# OSSICommsNew.net
KiCad netlist of a schematic drawn in EAGLE
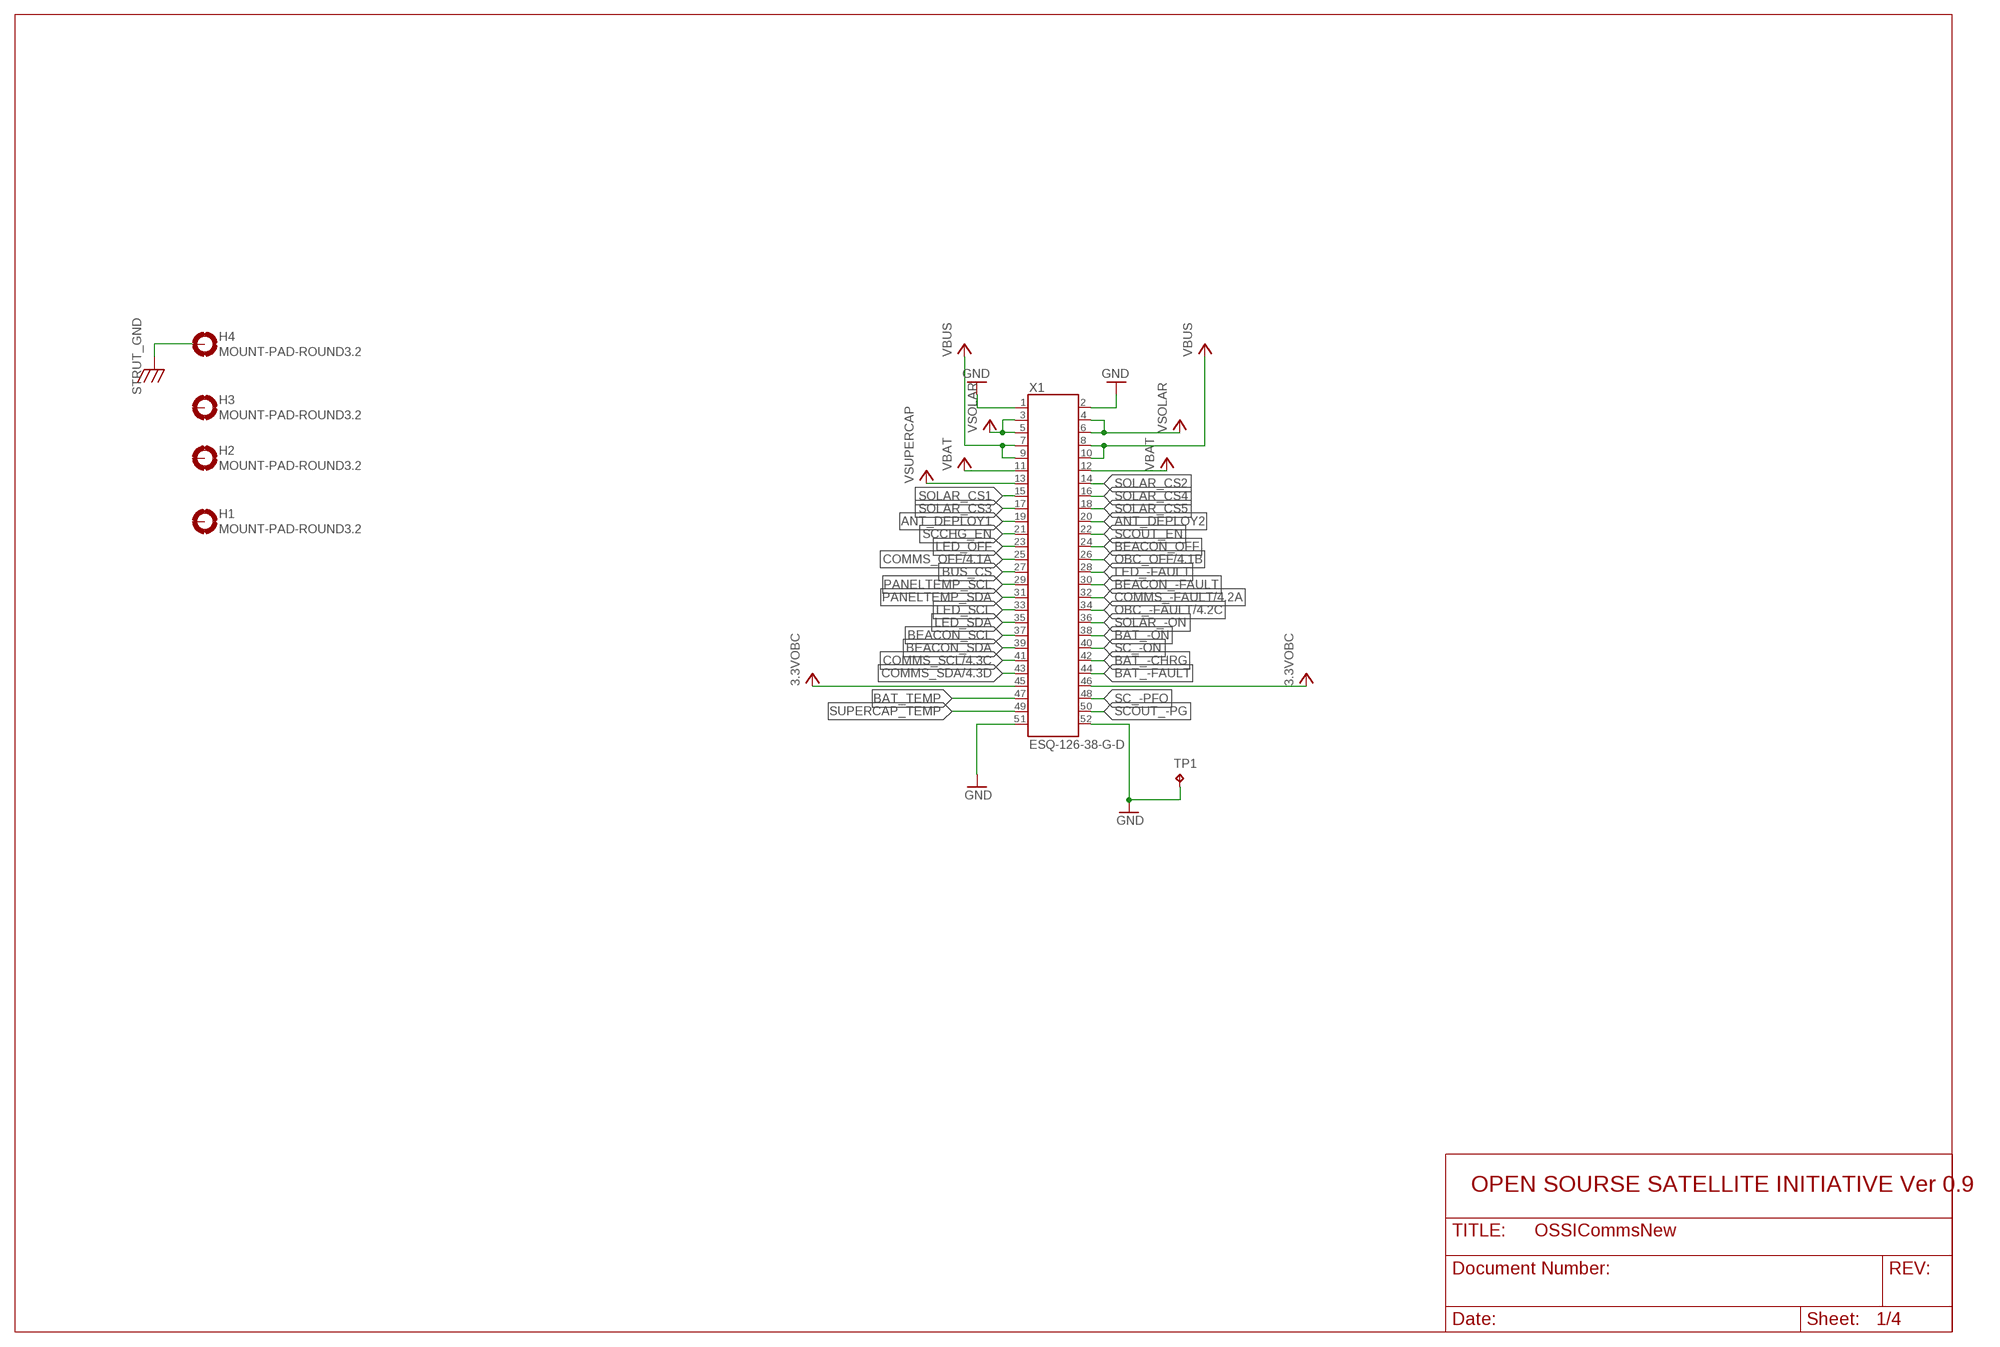
[diagram p0: schematic, sheet 1]
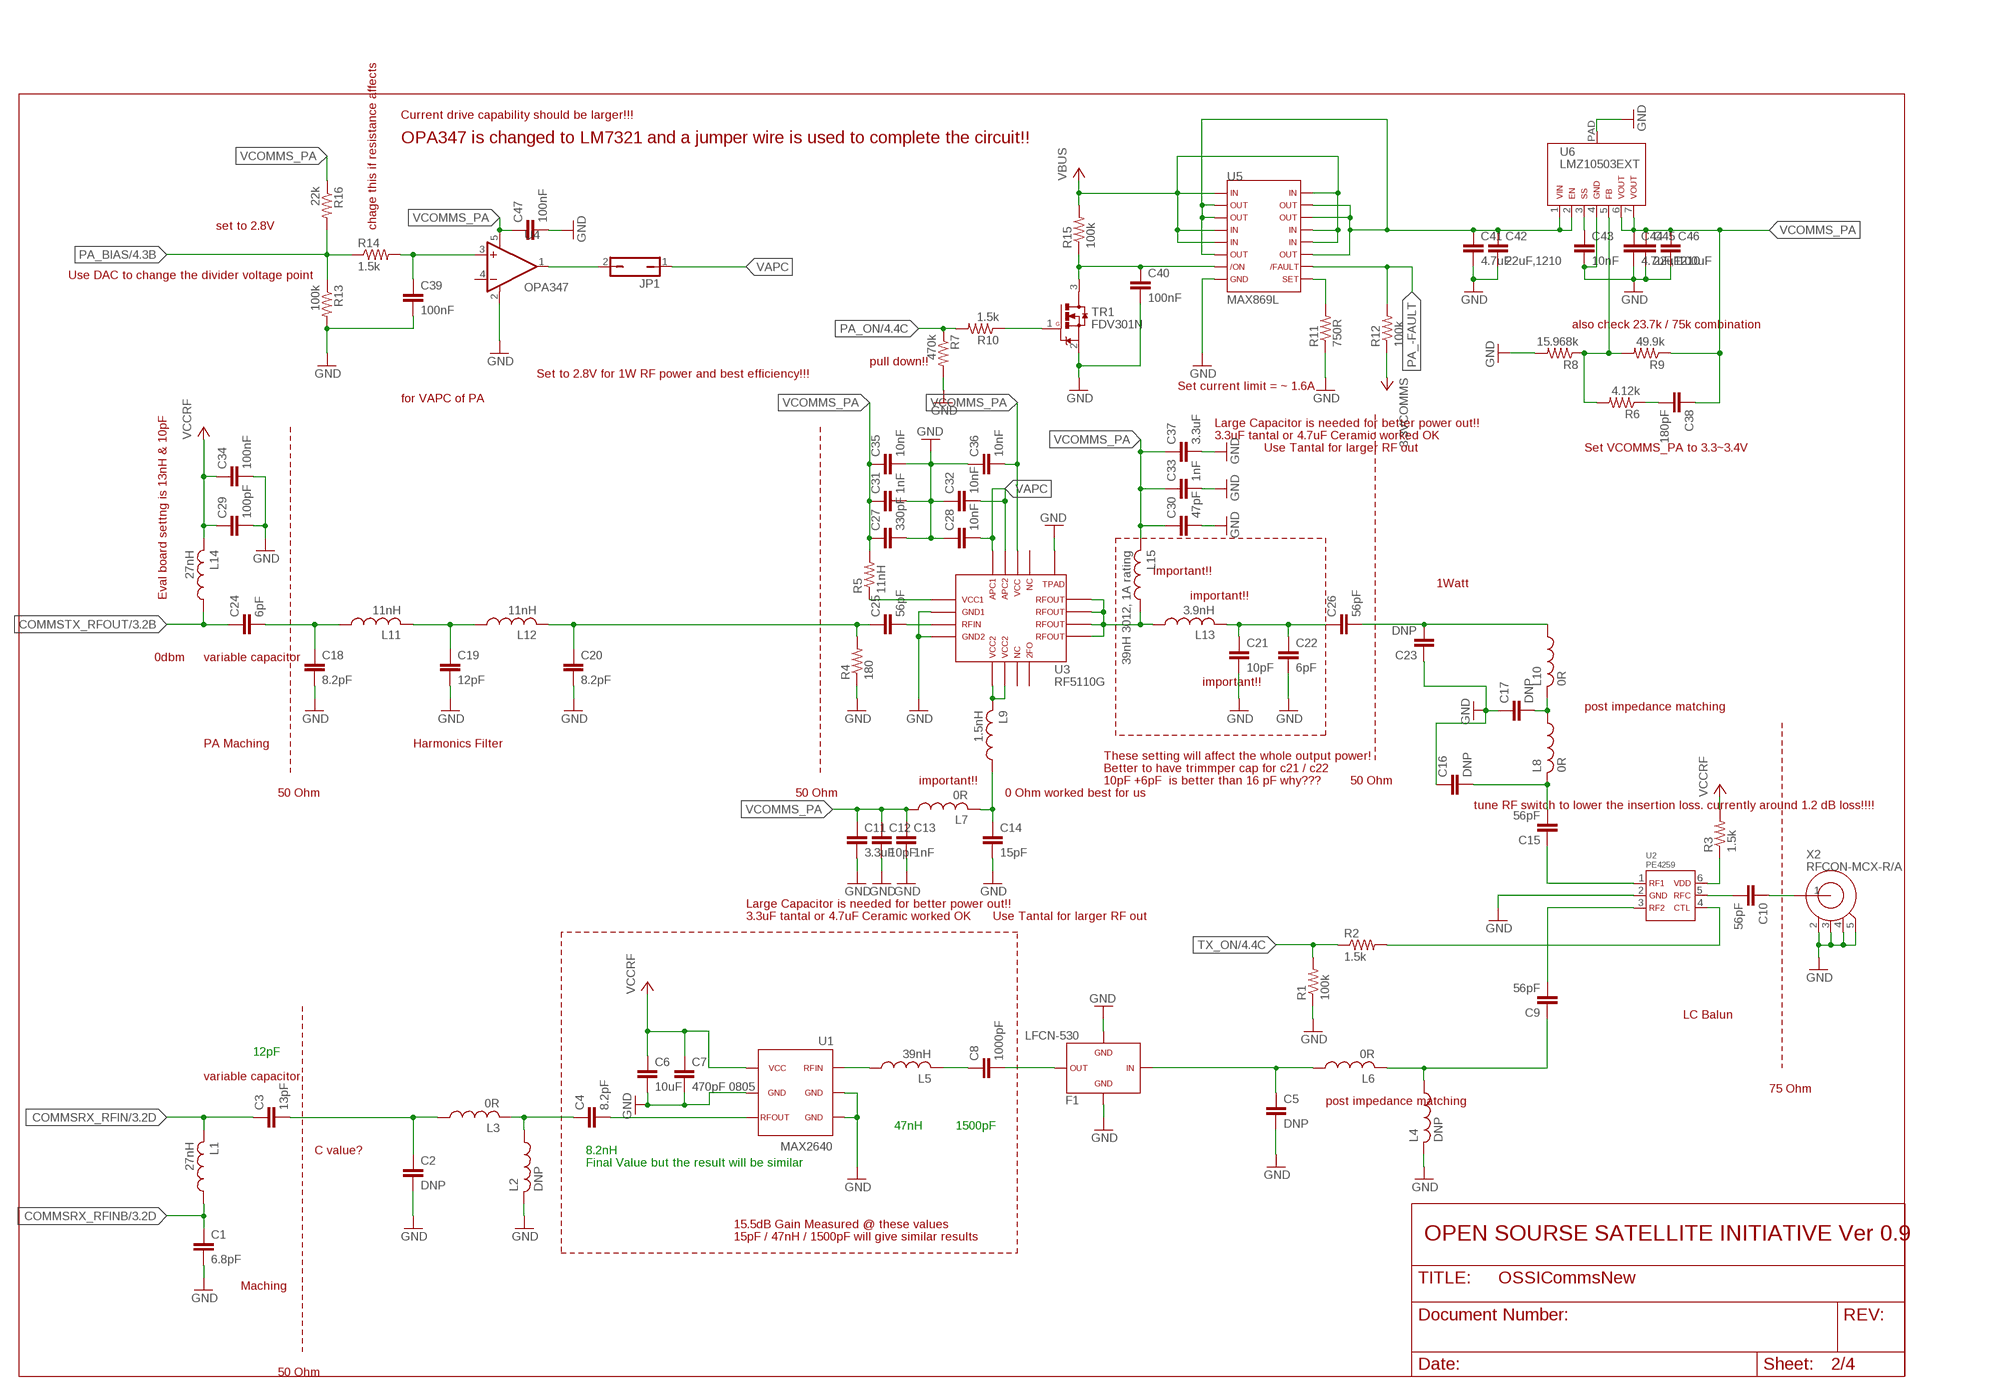
[diagram p1: schematic, sheet 2]
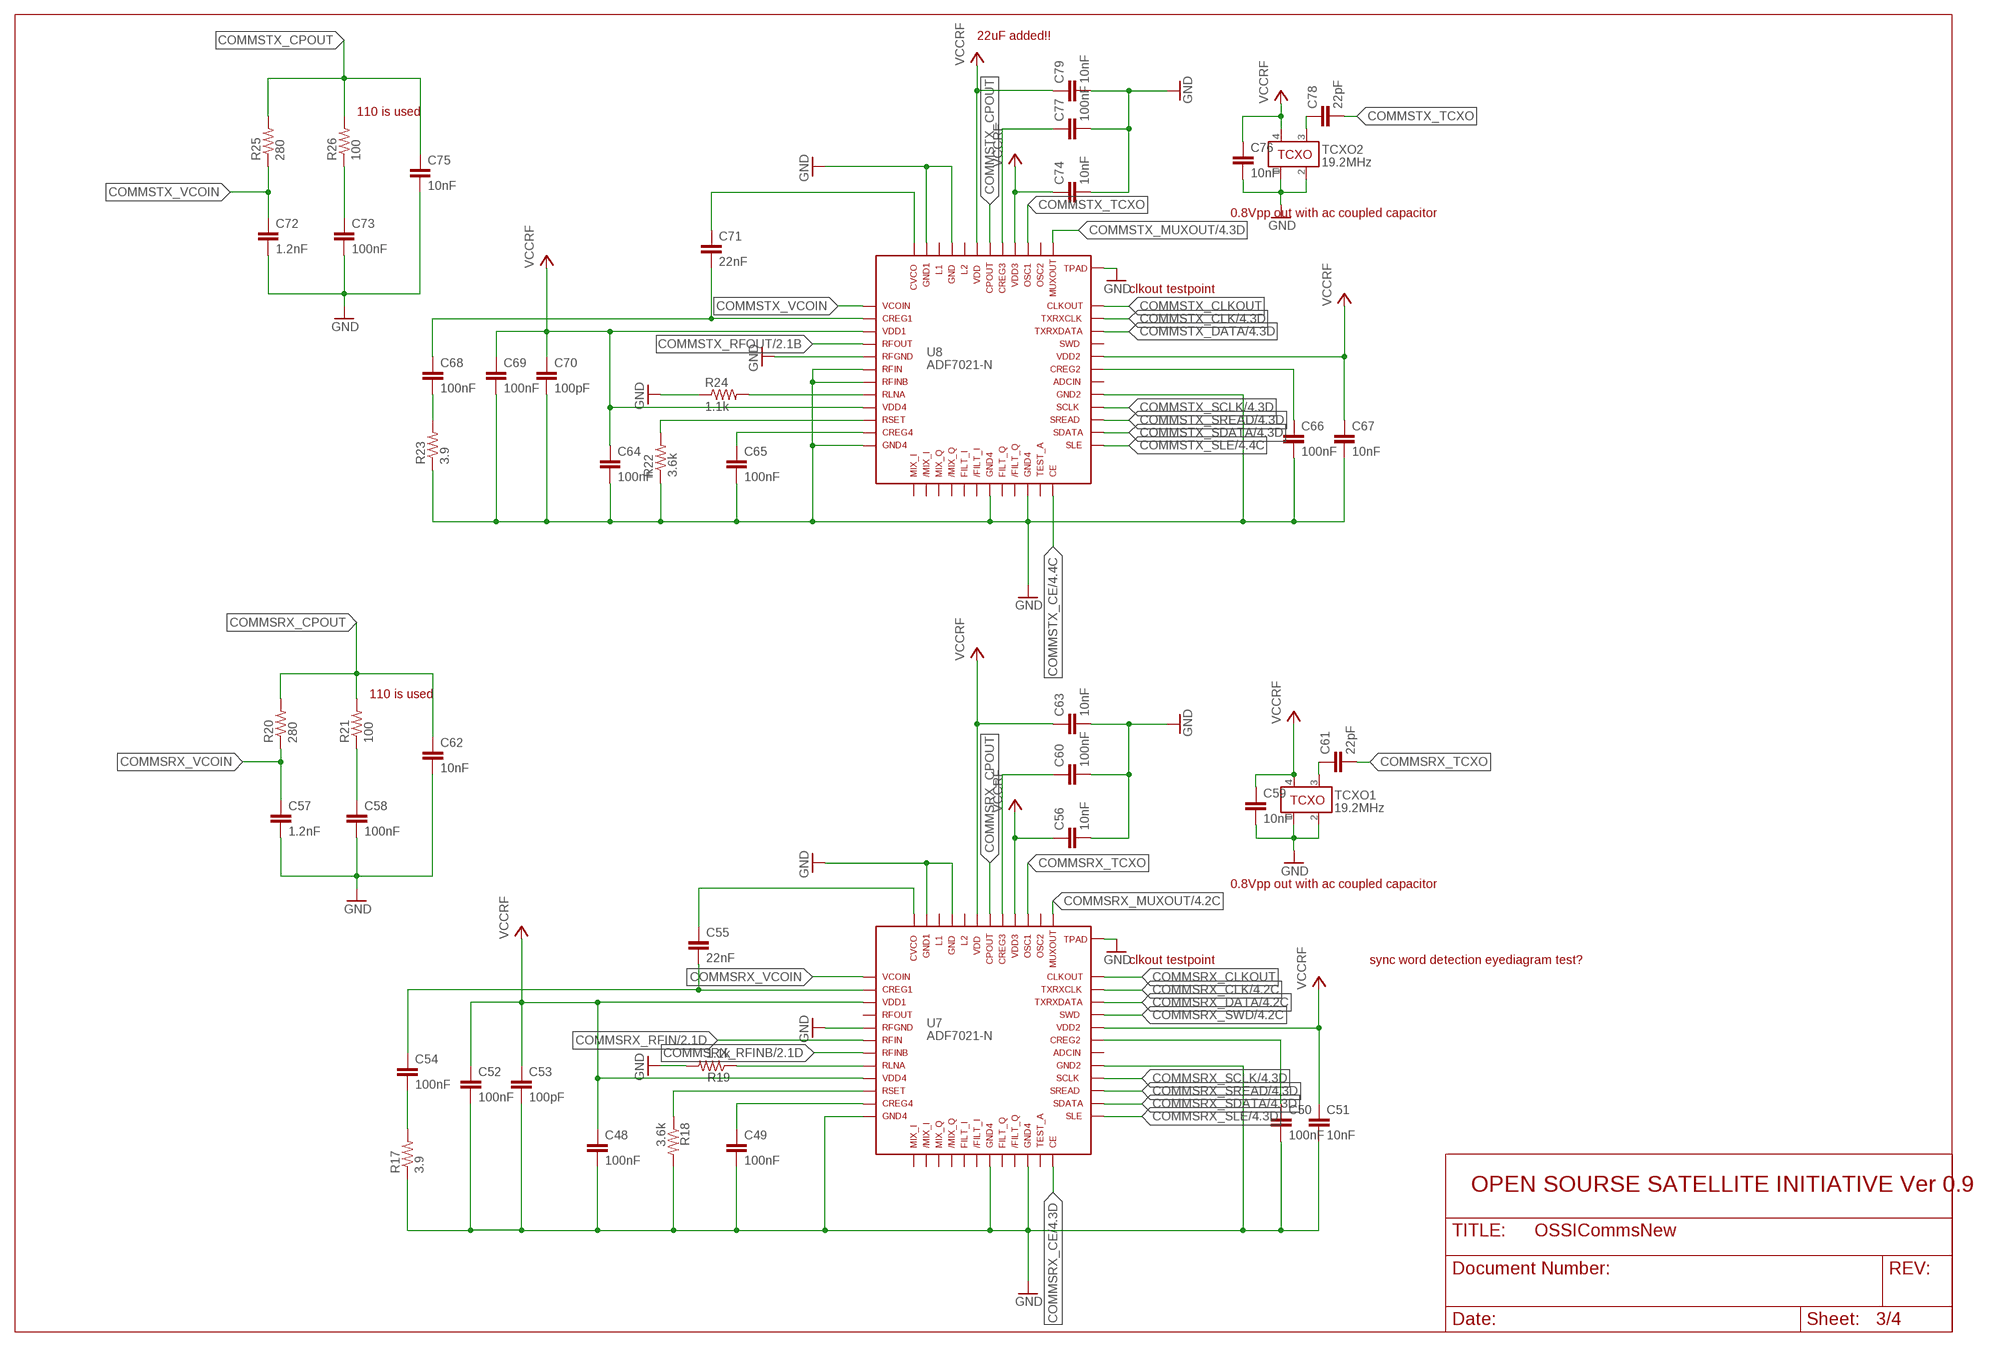
[diagram p2: schematic, sheet 3]
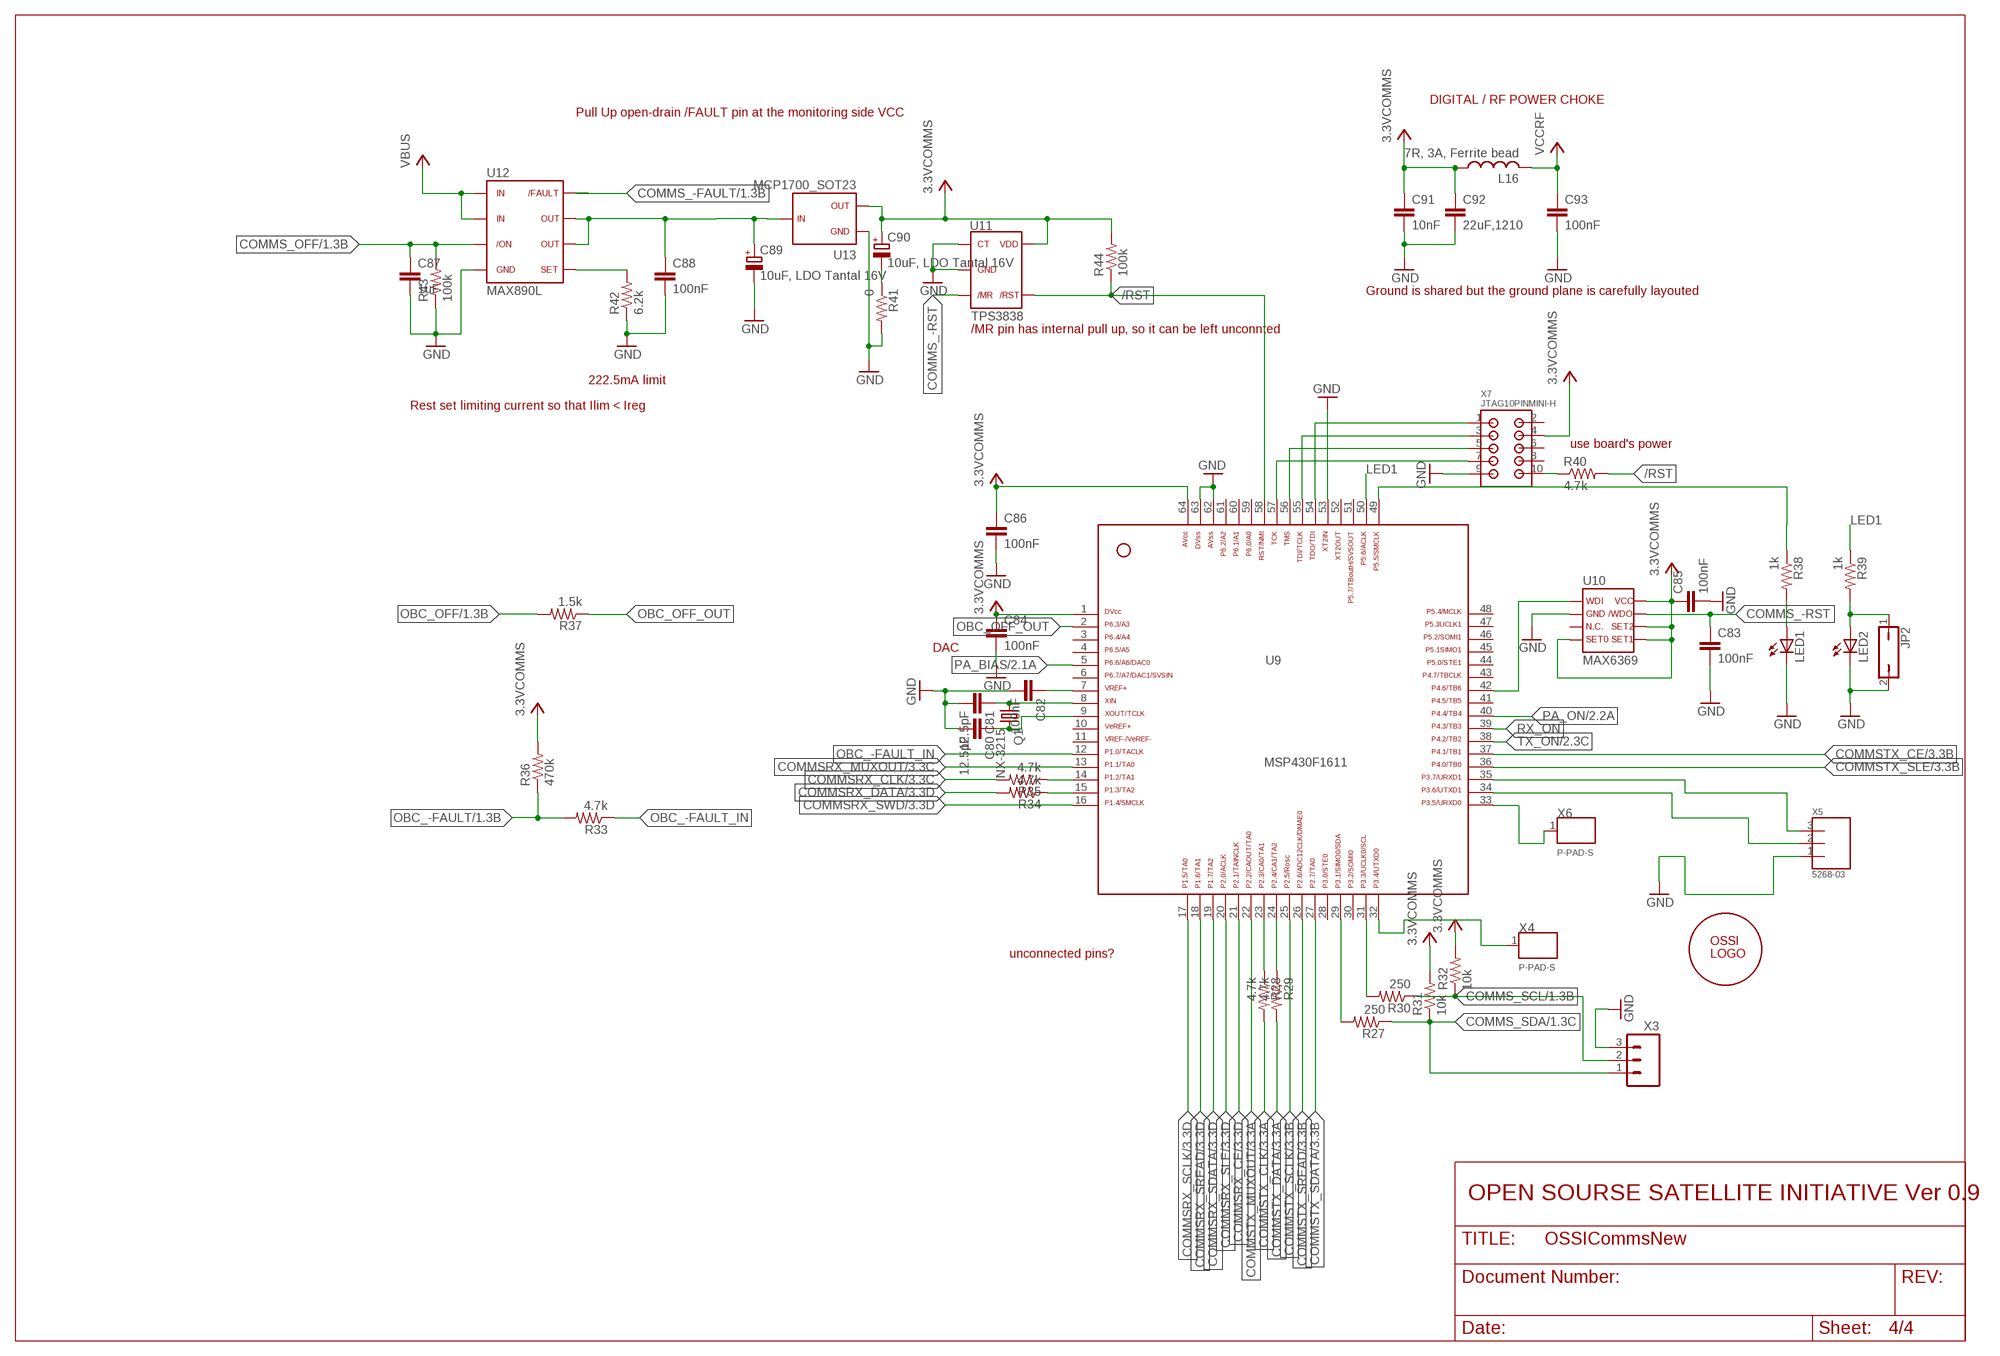
[diagram p3: schematic, sheet 4]

(export (version "E")
  (design (tool "Eeschema 10.0.6"))
  (components
    (comp (ref "C1")
      (value "6.8pF")
      (footprint "eagle-import:C0603(1608)")
      (libsource (lib "eagle-import") (part "C0603(1608)"))
    )
    (comp (ref "C2")
      (value "DNP")
      (footprint "eagle-import:C0603(1608)")
      (libsource (lib "eagle-import") (part "C0603(1608)"))
    )
    (comp (ref "C3")
      (value "13pF")
      (footprint "eagle-import:C0603(1608)")
      (libsource (lib "eagle-import") (part "C0603(1608)"))
    )
    (comp (ref "C4")
      (value "8.2pF")
      (footprint "eagle-import:C0603(1608)")
      (libsource (lib "eagle-import") (part "C0603(1608)"))
    )
    (comp (ref "C5")
      (value "DNP")
      (footprint "eagle-import:C0603(1608)")
      (libsource (lib "eagle-import") (part "C0603(1608)"))
    )
    (comp (ref "C6")
      (value "10uF")
      (footprint "eagle-import:C1206-GCM31")
      (libsource (lib "eagle-import") (part "C1206(3216)-GCM31"))
    )
    (comp (ref "C7")
      (value "470pF 0805")
      (footprint "eagle-import:C0805(2012)")
      (libsource (lib "eagle-import") (part "C0805(2012)"))
    )
    (comp (ref "C8")
      (value "1000pF")
      (footprint "eagle-import:C0603(1608)")
      (libsource (lib "eagle-import") (part "C0603(1608)"))
    )
    (comp (ref "C9")
      (value "56pF")
      (footprint "eagle-import:C0603(1608)")
      (libsource (lib "eagle-import") (part "C0603(1608)"))
    )
    (comp (ref "C10")
      (value "56pF")
      (footprint "eagle-import:C0603(1608)")
      (libsource (lib "eagle-import") (part "C0603(1608)"))
    )
    (comp (ref "C11")
      (value "3.3uF")
      (footprint "eagle-import:C1210-TMK325")
      (libsource (lib "eagle-import") (part "C1210(3225)-TMK325"))
    )
    (comp (ref "C12")
      (value "10pF")
      (footprint "eagle-import:C0603(1608)")
      (libsource (lib "eagle-import") (part "C0603(1608)"))
    )
    (comp (ref "C13")
      (value "1nF")
      (footprint "eagle-import:C0603(1608)")
      (libsource (lib "eagle-import") (part "C0603(1608)"))
    )
    (comp (ref "C14")
      (value "15pF")
      (footprint "eagle-import:C0603(1608)")
      (libsource (lib "eagle-import") (part "C0603(1608)"))
    )
    (comp (ref "C15")
      (value "56pF")
      (footprint "eagle-import:C0603(1608)")
      (libsource (lib "eagle-import") (part "C0603(1608)"))
    )
    (comp (ref "C16")
      (value "DNP")
      (footprint "eagle-import:C0603(1608)")
      (libsource (lib "eagle-import") (part "C0603(1608)"))
    )
    (comp (ref "C17")
      (value "DNP")
      (footprint "eagle-import:C0603(1608)")
      (libsource (lib "eagle-import") (part "C0603(1608)"))
    )
    (comp (ref "C18")
      (value "8.2pF")
      (footprint "eagle-import:C0603(1608)")
      (libsource (lib "eagle-import") (part "C0603(1608)"))
    )
    (comp (ref "C19")
      (value "12pF")
      (footprint "eagle-import:C0603(1608)")
      (libsource (lib "eagle-import") (part "C0603(1608)"))
    )
    (comp (ref "C20")
      (value "8.2pF")
      (footprint "eagle-import:C0603(1608)")
      (libsource (lib "eagle-import") (part "C0603(1608)"))
    )
    (comp (ref "C21")
      (value "10pF")
      (footprint "eagle-import:C0603(1608)")
      (libsource (lib "eagle-import") (part "C0603(1608)"))
    )
    (comp (ref "C22")
      (value "6pF")
      (footprint "eagle-import:C0603(1608)")
      (libsource (lib "eagle-import") (part "C0603(1608)"))
    )
    (comp (ref "C23")
      (value "DNP")
      (footprint "eagle-import:C0603(1608)")
      (libsource (lib "eagle-import") (part "C0603(1608)"))
    )
    (comp (ref "C24")
      (value "6pF")
      (footprint "eagle-import:C0603(1608)")
      (libsource (lib "eagle-import") (part "C0603(1608)"))
    )
    (comp (ref "C25")
      (value "56pF")
      (footprint "eagle-import:C0603(1608)")
      (libsource (lib "eagle-import") (part "C0603(1608)"))
    )
    (comp (ref "C26")
      (value "56pF")
      (footprint "eagle-import:C0603(1608)")
      (libsource (lib "eagle-import") (part "C0603(1608)"))
    )
    (comp (ref "C27")
      (value "330pF")
      (footprint "eagle-import:C0603(1608)")
      (libsource (lib "eagle-import") (part "C0603(1608)"))
    )
    (comp (ref "C28")
      (value "10nF")
      (footprint "eagle-import:C0603(1608)")
      (libsource (lib "eagle-import") (part "C0603(1608)"))
    )
    (comp (ref "C29")
      (value "100pF")
      (footprint "eagle-import:C0603(1608)")
      (libsource (lib "eagle-import") (part "C0603(1608)"))
    )
    (comp (ref "C30")
      (value "47pF")
      (footprint "eagle-import:C0603(1608)")
      (libsource (lib "eagle-import") (part "C0603(1608)"))
    )
    (comp (ref "C31")
      (value "1nF")
      (footprint "eagle-import:C0603(1608)")
      (libsource (lib "eagle-import") (part "C0603(1608)"))
    )
    (comp (ref "C32")
      (value "10nF")
      (footprint "eagle-import:C0603(1608)")
      (libsource (lib "eagle-import") (part "C0603(1608)"))
    )
    (comp (ref "C33")
      (value "1nF")
      (footprint "eagle-import:C0603(1608)")
      (libsource (lib "eagle-import") (part "C0603(1608)"))
    )
    (comp (ref "C34")
      (value "100nF")
      (footprint "eagle-import:C0603(1608)")
      (libsource (lib "eagle-import") (part "C0603(1608)"))
    )
    (comp (ref "C35")
      (value "10nF")
      (footprint "eagle-import:C0603(1608)")
      (libsource (lib "eagle-import") (part "C0603(1608)"))
    )
    (comp (ref "C36")
      (value "10nF")
      (footprint "eagle-import:C0603(1608)")
      (libsource (lib "eagle-import") (part "C0603(1608)"))
    )
    (comp (ref "C37")
      (value "3.3uF")
      (footprint "eagle-import:C1210-TMK325")
      (libsource (lib "eagle-import") (part "C1210(3225)-TMK325"))
    )
    (comp (ref "C38")
      (value "180pF")
      (footprint "eagle-import:C0603(1608)")
      (libsource (lib "eagle-import") (part "C0603(1608)"))
    )
    (comp (ref "C39")
      (value "100nF")
      (footprint "eagle-import:C0603(1608)")
      (libsource (lib "eagle-import") (part "C0603(1608)"))
    )
    (comp (ref "C40")
      (value "100nF")
      (footprint "eagle-import:C0603(1608)")
      (libsource (lib "eagle-import") (part "C0603(1608)"))
    )
    (comp (ref "C41")
      (value "4.7uF")
      (footprint "eagle-import:C1210-GCM32")
      (libsource (lib "eagle-import") (part "C1210(3225)-GCM32"))
    )
    (comp (ref "C42")
      (value "22uF,1210")
      (footprint "eagle-import:C1210-GCM32")
      (libsource (lib "eagle-import") (part "C1210(3225)-GCM32"))
    )
    (comp (ref "C43")
      (value "10nF")
      (footprint "eagle-import:C0603(1608)")
      (libsource (lib "eagle-import") (part "C0603(1608)"))
    )
    (comp (ref "C44")
      (value "4.7uF,1210")
      (footprint "eagle-import:C0805(2012)")
      (libsource (lib "eagle-import") (part "C0805(2012)"))
    )
    (comp (ref "C45")
      (value "22uF")
      (footprint "eagle-import:C1210-GCM32")
      (libsource (lib "eagle-import") (part "C1210(3225)-GCM32"))
    )
    (comp (ref "C46")
      (value "100uF")
      (footprint "eagle-import:C1210-GCM32")
      (libsource (lib "eagle-import") (part "C1210(3225)-GCM32"))
    )
    (comp (ref "C47")
      (value "100nF")
      (footprint "eagle-import:C0603(1608)")
      (libsource (lib "eagle-import") (part "C0603(1608)"))
    )
    (comp (ref "F1")
      (value "LFCN-530")
      (footprint "eagle-import:LFCN")
      (libsource (lib "eagle-import") (part "LFCN-160"))
    )
    (comp (ref "JP1")
      (value "JP1Q")
      (footprint "eagle-import:JP1")
      (libsource (lib "eagle-import") (part "JP1Q"))
    )
    (comp (ref "L1")
      (value "27nH")
      (footprint "eagle-import:L0603(1608)")
      (libsource (lib "eagle-import") (part "L0603(1608)"))
    )
    (comp (ref "L2")
      (value "DNP")
      (footprint "eagle-import:L0603(1608)")
      (libsource (lib "eagle-import") (part "L0603(1608)"))
    )
    (comp (ref "L3")
      (value "0R")
      (footprint "eagle-import:L0603(1608)")
      (libsource (lib "eagle-import") (part "L0603(1608)"))
    )
    (comp (ref "L4")
      (value "DNP")
      (footprint "eagle-import:L0603(1608)")
      (libsource (lib "eagle-import") (part "L0603(1608)"))
    )
    (comp (ref "L5")
      (value "39nH")
      (footprint "eagle-import:L0603(1608)")
      (libsource (lib "eagle-import") (part "L0603(1608)"))
    )
    (comp (ref "L6")
      (value "0R")
      (footprint "eagle-import:L0603(1608)")
      (libsource (lib "eagle-import") (part "L0603(1608)"))
    )
    (comp (ref "L7")
      (value "0R")
      (footprint "eagle-import:LQH32CN331K23L")
      (libsource (lib "eagle-import") (part "LLQH32CN"))
    )
    (comp (ref "L8")
      (value "0R")
      (footprint "eagle-import:L0603(1608)")
      (libsource (lib "eagle-import") (part "L0603(1608)"))
    )
    (comp (ref "L9")
      (value "1.5nH")
      (footprint "eagle-import:L0603(1608)")
      (libsource (lib "eagle-import") (part "L0603(1608)"))
    )
    (comp (ref "L10")
      (value "0R")
      (footprint "eagle-import:L0603(1608)")
      (libsource (lib "eagle-import") (part "L0603(1608)"))
    )
    (comp (ref "L11")
      (value "11nH")
      (footprint "eagle-import:L0603(1608)")
      (libsource (lib "eagle-import") (part "L0603(1608)"))
    )
    (comp (ref "L12")
      (value "11nH")
      (footprint "eagle-import:L0603(1608)")
      (libsource (lib "eagle-import") (part "L0603(1608)"))
    )
    (comp (ref "L13")
      (value "3.9nH")
      (footprint "eagle-import:L0603(1608)")
      (libsource (lib "eagle-import") (part "L0603(1608)"))
    )
    (comp (ref "L14")
      (value "27nH")
      (footprint "eagle-import:L0603(1608)")
      (libsource (lib "eagle-import") (part "L0603(1608)"))
    )
    (comp (ref "L15")
      (value "39nH 3012, 1A rating")
      (footprint "eagle-import:NR3012")
      (libsource (lib "eagle-import") (part "LNR3012"))
    )
    (comp (ref "R1")
      (value "100k")
      (footprint "eagle-import:R0603(1608)")
      (libsource (lib "eagle-import") (part "R0603(1608)"))
    )
    (comp (ref "R2")
      (value "1.5k")
      (footprint "eagle-import:R0603(1608)")
      (libsource (lib "eagle-import") (part "R0603(1608)"))
    )
    (comp (ref "R3")
      (value "1.5k")
      (footprint "eagle-import:R0603(1608)")
      (libsource (lib "eagle-import") (part "R0603(1608)"))
    )
    (comp (ref "R4")
      (value "180")
      (footprint "eagle-import:R0603(1608)")
      (libsource (lib "eagle-import") (part "R0603(1608)"))
    )
    (comp (ref "R5")
      (value "11nH")
      (footprint "eagle-import:R0603(1608)")
      (libsource (lib "eagle-import") (part "R0603(1608)"))
    )
    (comp (ref "R6")
      (value "4.12k")
      (footprint "eagle-import:R0603(1608)")
      (libsource (lib "eagle-import") (part "R0603(1608)"))
    )
    (comp (ref "R7")
      (value "470k")
      (footprint "eagle-import:R0603(1608)")
      (libsource (lib "eagle-import") (part "R0603(1608)"))
    )
    (comp (ref "R8")
      (value "15.968k")
      (footprint "eagle-import:R0603(1608)")
      (libsource (lib "eagle-import") (part "R0603(1608)"))
    )
    (comp (ref "R9")
      (value "49.9k")
      (footprint "eagle-import:R0603(1608)")
      (libsource (lib "eagle-import") (part "R0603(1608)"))
    )
    (comp (ref "R10")
      (value "1.5k")
      (footprint "eagle-import:R0603(1608)")
      (libsource (lib "eagle-import") (part "R0603(1608)"))
    )
    (comp (ref "R11")
      (value "750R")
      (footprint "eagle-import:R0603(1608)")
      (libsource (lib "eagle-import") (part "R0603(1608)"))
    )
    (comp (ref "R12")
      (value "100k")
      (footprint "eagle-import:R0603(1608)")
      (libsource (lib "eagle-import") (part "R0603(1608)"))
    )
    (comp (ref "R13")
      (value "100k")
      (footprint "eagle-import:R0603(1608)")
      (libsource (lib "eagle-import") (part "R0603(1608)"))
    )
    (comp (ref "R14")
      (value "1.5k")
      (footprint "eagle-import:R0603(1608)")
      (libsource (lib "eagle-import") (part "R0603(1608)"))
    )
    (comp (ref "R15")
      (value "100k")
      (footprint "eagle-import:R0603(1608)")
      (libsource (lib "eagle-import") (part "R0603(1608)"))
    )
    (comp (ref "R16")
      (value "22k")
      (footprint "eagle-import:R0603(1608)")
      (libsource (lib "eagle-import") (part "R0603(1608)"))
    )
    (comp (ref "TR1")
      (value "FDV301N")
      (footprint "eagle-import:SOT23")
      (libsource (lib "eagle-import") (part "FDV301N"))
    )
    (comp (ref "U1")
      (value "MAX2640")
      (footprint "eagle-import:SOT23-6")
      (libsource (lib "eagle-import") (part "MAX2640"))
    )
    (comp (ref "U2")
      (value "PE4259")
      (footprint "eagle-import:SC70-6")
      (libsource (lib "eagle-import") (part "PE4259"))
    )
    (comp (ref "U3")
      (value "RF5110G")
      (footprint "eagle-import:RF5110G")
      (libsource (lib "eagle-import") (part "RF5110G"))
    )
    (comp (ref "U4")
      (value "OPA347")
      (footprint "eagle-import:SOT23-5DBV")
      (libsource (lib "eagle-import") (part "OPA347"))
    )
    (comp (ref "U5")
      (value "MAX869L")
      (footprint "eagle-import:16QSOP")
      (libsource (lib "eagle-import") (part "MAX869L"))
    )
    (comp (ref "U6")
      (value "LMZ10503EXT")
      (footprint "eagle-import:TO-PMOD-7")
      (libsource (lib "eagle-import") (part "LMZ10503EXT"))
    )
    (comp (ref "X2")
      (value "RFCON-MCX-R/A")
      (footprint "eagle-import:MCX-R_A")
      (libsource (lib "eagle-import") (part "RFCON-MCX-R/A"))
    )
    (comp (ref "H1")
      (value "MOUNT-PAD-ROUND3.2")
      (footprint "eagle-import:3.2-PAD-ROUND")
      (libsource (lib "eagle-import") (part "MOUNT-PAD-ROUND3.2"))
    )
    (comp (ref "H2")
      (value "MOUNT-PAD-ROUND3.2")
      (footprint "eagle-import:3.2-PAD-ROUND")
      (libsource (lib "eagle-import") (part "MOUNT-PAD-ROUND3.2"))
    )
    (comp (ref "H3")
      (value "MOUNT-PAD-ROUND3.2")
      (footprint "eagle-import:3.2-PAD-ROUND")
      (libsource (lib "eagle-import") (part "MOUNT-PAD-ROUND3.2"))
    )
    (comp (ref "H4")
      (value "MOUNT-PAD-ROUND3.2")
      (footprint "eagle-import:3.2-PAD-ROUND")
      (libsource (lib "eagle-import") (part "MOUNT-PAD-ROUND3.2"))
    )
    (comp (ref "TP1")
      (value "TP")
      (footprint "eagle-import:TP-13")
      (libsource (lib "eagle-import") (part "TP"))
    )
    (comp (ref "X1")
      (value "ESQ-126-38-G-D")
      (footprint "eagle-import:ESQ-126-XX-X-D")
      (libsource (lib "eagle-import") (part "ESQ-126-38-G-D"))
    )
    (comp (ref "C48")
      (value "100nF")
      (footprint "eagle-import:C0603(1608)")
      (libsource (lib "eagle-import") (part "C0603(1608)"))
    )
    (comp (ref "C49")
      (value "100nF")
      (footprint "eagle-import:C0603(1608)")
      (libsource (lib "eagle-import") (part "C0603(1608)"))
    )
    (comp (ref "C50")
      (value "100nF")
      (footprint "eagle-import:C0603(1608)")
      (libsource (lib "eagle-import") (part "C0603(1608)"))
    )
    (comp (ref "C51")
      (value "10nF")
      (footprint "eagle-import:C0603(1608)")
      (libsource (lib "eagle-import") (part "C0603(1608)"))
    )
    (comp (ref "C52")
      (value "100nF")
      (footprint "eagle-import:C0603(1608)")
      (libsource (lib "eagle-import") (part "C0603(1608)"))
    )
    (comp (ref "C53")
      (value "100pF")
      (footprint "eagle-import:C0603(1608)")
      (libsource (lib "eagle-import") (part "C0603(1608)"))
    )
    (comp (ref "C54")
      (value "100nF")
      (footprint "eagle-import:C0603(1608)")
      (libsource (lib "eagle-import") (part "C0603(1608)"))
    )
    (comp (ref "C55")
      (value "22nF")
      (footprint "eagle-import:C0603(1608)")
      (libsource (lib "eagle-import") (part "C0603(1608)"))
    )
    (comp (ref "C56")
      (value "10nF")
      (footprint "eagle-import:C0603(1608)")
      (libsource (lib "eagle-import") (part "C0603(1608)"))
    )
    (comp (ref "C57")
      (value "1.2nF")
      (footprint "eagle-import:C0603(1608)")
      (libsource (lib "eagle-import") (part "C0603(1608)"))
    )
    (comp (ref "C58")
      (value "100nF")
      (footprint "eagle-import:C0603(1608)")
      (libsource (lib "eagle-import") (part "C0603(1608)"))
    )
    (comp (ref "C59")
      (value "10nF")
      (footprint "eagle-import:C0603(1608)")
      (libsource (lib "eagle-import") (part "C0603(1608)"))
    )
    (comp (ref "C60")
      (value "100nF")
      (footprint "eagle-import:C0603(1608)")
      (libsource (lib "eagle-import") (part "C0603(1608)"))
    )
    (comp (ref "C61")
      (value "22pF")
      (footprint "eagle-import:C0603(1608)")
      (libsource (lib "eagle-import") (part "C0603(1608)"))
    )
    (comp (ref "C62")
      (value "10nF")
      (footprint "eagle-import:C0603(1608)")
      (libsource (lib "eagle-import") (part "C0603(1608)"))
    )
    (comp (ref "C63")
      (value "10nF")
      (footprint "eagle-import:C0603(1608)")
      (libsource (lib "eagle-import") (part "C0603(1608)"))
    )
    (comp (ref "C64")
      (value "100nF")
      (footprint "eagle-import:C0603(1608)")
      (libsource (lib "eagle-import") (part "C0603(1608)"))
    )
    (comp (ref "C65")
      (value "100nF")
      (footprint "eagle-import:C0603(1608)")
      (libsource (lib "eagle-import") (part "C0603(1608)"))
    )
    (comp (ref "C66")
      (value "100nF")
      (footprint "eagle-import:C0603(1608)")
      (libsource (lib "eagle-import") (part "C0603(1608)"))
    )
    (comp (ref "C67")
      (value "10nF")
      (footprint "eagle-import:C0603(1608)")
      (libsource (lib "eagle-import") (part "C0603(1608)"))
    )
    (comp (ref "C68")
      (value "100nF")
      (footprint "eagle-import:C0603(1608)")
      (libsource (lib "eagle-import") (part "C0603(1608)"))
    )
    (comp (ref "C69")
      (value "100nF")
      (footprint "eagle-import:C0603(1608)")
      (libsource (lib "eagle-import") (part "C0603(1608)"))
    )
    (comp (ref "C70")
      (value "100pF")
      (footprint "eagle-import:C0603(1608)")
      (libsource (lib "eagle-import") (part "C0603(1608)"))
    )
    (comp (ref "C71")
      (value "22nF")
      (footprint "eagle-import:C0603(1608)")
      (libsource (lib "eagle-import") (part "C0603(1608)"))
    )
    (comp (ref "C72")
      (value "1.2nF")
      (footprint "eagle-import:C0603(1608)")
      (libsource (lib "eagle-import") (part "C0603(1608)"))
    )
    (comp (ref "C73")
      (value "100nF")
      (footprint "eagle-import:C0603(1608)")
      (libsource (lib "eagle-import") (part "C0603(1608)"))
    )
    (comp (ref "C74")
      (value "10nF")
      (footprint "eagle-import:C0603(1608)")
      (libsource (lib "eagle-import") (part "C0603(1608)"))
    )
    (comp (ref "C75")
      (value "10nF")
      (footprint "eagle-import:C0603(1608)")
      (libsource (lib "eagle-import") (part "C0603(1608)"))
    )
    (comp (ref "C76")
      (value "10nF")
      (footprint "eagle-import:C0603(1608)")
      (libsource (lib "eagle-import") (part "C0603(1608)"))
    )
    (comp (ref "C77")
      (value "100nF")
      (footprint "eagle-import:C0603(1608)")
      (libsource (lib "eagle-import") (part "C0603(1608)"))
    )
    (comp (ref "C78")
      (value "22pF")
      (footprint "eagle-import:C0603(1608)")
      (libsource (lib "eagle-import") (part "C0603(1608)"))
    )
    (comp (ref "C79")
      (value "10nF")
      (footprint "eagle-import:C0603(1608)")
      (libsource (lib "eagle-import") (part "C0603(1608)"))
    )
    (comp (ref "R17")
      (value "3.9")
      (footprint "eagle-import:R0603(1608)")
      (libsource (lib "eagle-import") (part "R0603(1608)"))
    )
    (comp (ref "R18")
      (value "3.6k")
      (footprint "eagle-import:R0603(1608)")
      (libsource (lib "eagle-import") (part "R0603(1608)"))
    )
    (comp (ref "R19")
      (value "1.1k")
      (footprint "eagle-import:R0603(1608)")
      (libsource (lib "eagle-import") (part "R0603(1608)"))
    )
    (comp (ref "R20")
      (value "280")
      (footprint "eagle-import:R0603(1608)")
      (libsource (lib "eagle-import") (part "R0603(1608)"))
    )
    (comp (ref "R21")
      (value "100")
      (footprint "eagle-import:R0603(1608)")
      (libsource (lib "eagle-import") (part "R0603(1608)"))
    )
    (comp (ref "R22")
      (value "3.6k")
      (footprint "eagle-import:R0603(1608)")
      (libsource (lib "eagle-import") (part "R0603(1608)"))
    )
    (comp (ref "R23")
      (value "3.9")
      (footprint "eagle-import:R0603(1608)")
      (libsource (lib "eagle-import") (part "R0603(1608)"))
    )
    (comp (ref "R24")
      (value "1.1k")
      (footprint "eagle-import:R0603(1608)")
      (libsource (lib "eagle-import") (part "R0603(1608)"))
    )
    (comp (ref "R25")
      (value "280")
      (footprint "eagle-import:R0603(1608)")
      (libsource (lib "eagle-import") (part "R0603(1608)"))
    )
    (comp (ref "R26")
      (value "100")
      (footprint "eagle-import:R0603(1608)")
      (libsource (lib "eagle-import") (part "R0603(1608)"))
    )
    (comp (ref "TCXO1")
      (value "19.2MHz")
      (footprint "eagle-import:TCXO_M532")
      (libsource (lib "eagle-import") (part "TCXO-M532"))
    )
    (comp (ref "TCXO2")
      (value "19.2MHz")
      (footprint "eagle-import:TCXO_M532")
      (libsource (lib "eagle-import") (part "TCXO-M532"))
    )
    (comp (ref "U7")
      (value "ADF7021-N")
      (footprint "eagle-import:LFCSP48")
      (libsource (lib "eagle-import") (part "ADF7021-N"))
    )
    (comp (ref "U8")
      (value "ADF7021-N")
      (footprint "eagle-import:LFCSP48")
      (libsource (lib "eagle-import") (part "ADF7021-N"))
    )
    (comp (ref "C80")
      (value "12.5pF")
      (footprint "eagle-import:C0603(1608)")
      (libsource (lib "eagle-import") (part "C0603(1608)"))
    )
    (comp (ref "C81")
      (value "12.5pF")
      (footprint "eagle-import:C0603(1608)")
      (libsource (lib "eagle-import") (part "C0603(1608)"))
    )
    (comp (ref "C82")
      (value "100nF")
      (footprint "eagle-import:C0603(1608)")
      (libsource (lib "eagle-import") (part "C0603(1608)"))
    )
    (comp (ref "C83")
      (value "100nF")
      (footprint "eagle-import:C0603(1608)")
      (libsource (lib "eagle-import") (part "C0603(1608)"))
    )
    (comp (ref "C84")
      (value "100nF")
      (footprint "eagle-import:C0603(1608)")
      (libsource (lib "eagle-import") (part "C0603(1608)"))
    )
    (comp (ref "C85")
      (value "100nF")
      (footprint "eagle-import:C0603(1608)")
      (libsource (lib "eagle-import") (part "C0603(1608)"))
    )
    (comp (ref "C86")
      (value "100nF")
      (footprint "eagle-import:C0603(1608)")
      (libsource (lib "eagle-import") (part "C0603(1608)"))
    )
    (comp (ref "C87")
      (value "1uF")
      (footprint "eagle-import:C0603(1608)")
      (libsource (lib "eagle-import") (part "C0603(1608)"))
    )
    (comp (ref "C88")
      (value "100nF")
      (footprint "eagle-import:C0603(1608)")
      (libsource (lib "eagle-import") (part "C0603(1608)"))
    )
    (comp (ref "C89")
      (value "10uF, LDO Tantal 16V")
      (footprint "eagle-import:C1206(3216)-A")
      (libsource (lib "eagle-import") (part "C-TANTAL-A"))
    )
    (comp (ref "C90")
      (value "10uF, LDO Tantal 16V")
      (footprint "eagle-import:C1206(3216)-A")
      (libsource (lib "eagle-import") (part "C-TANTAL-A"))
    )
    (comp (ref "C91")
      (value "10nF")
      (footprint "eagle-import:C0603(1608)")
      (libsource (lib "eagle-import") (part "C0603(1608)"))
    )
    (comp (ref "C92")
      (value "22uF,1210")
      (footprint "eagle-import:C1210-GCM32")
      (libsource (lib "eagle-import") (part "C1210(3225)-GCM32"))
    )
    (comp (ref "C93")
      (value "100nF")
      (footprint "eagle-import:C0603(1608)")
      (libsource (lib "eagle-import") (part "C0603(1608)"))
    )
    (comp (ref "JP2")
      (value "JP1Q")
      (footprint "eagle-import:JP1")
      (libsource (lib "eagle-import") (part "JP1Q"))
    )
    (comp (ref "L16")
      (value "7R, 3A, Ferrite bead")
      (footprint "eagle-import:L0805(2012)")
      (libsource (lib "eagle-import") (part "L0805(2012)"))
    )
    (comp (ref "LED1")
      (value "LEDCHIPLED_0603")
      (footprint "eagle-import:CHIPLED_0603")
      (libsource (lib "eagle-import") (part "LEDCHIPLED_0603"))
    )
    (comp (ref "LED2")
      (value "LEDCHIPLED_0603")
      (footprint "eagle-import:CHIPLED_0603")
      (libsource (lib "eagle-import") (part "LEDCHIPLED_0603"))
    )
    (comp (ref "Q1")
      (value "NX-3215")
      (footprint "eagle-import:NX-3215")
      (libsource (lib "eagle-import") (part "NX-3215"))
    )
    (comp (ref "R27")
      (value "250")
      (footprint "eagle-import:R0603(1608)")
      (libsource (lib "eagle-import") (part "R0603(1608)"))
    )
    (comp (ref "R28")
      (value "4.7k")
      (footprint "eagle-import:R0603(1608)")
      (libsource (lib "eagle-import") (part "R0603(1608)"))
    )
    (comp (ref "R29")
      (value "4.7k")
      (footprint "eagle-import:R0603(1608)")
      (libsource (lib "eagle-import") (part "R0603(1608)"))
    )
    (comp (ref "R30")
      (value "250")
      (footprint "eagle-import:R0603(1608)")
      (libsource (lib "eagle-import") (part "R0603(1608)"))
    )
    (comp (ref "R31")
      (value "10k")
      (footprint "eagle-import:R0603(1608)")
      (libsource (lib "eagle-import") (part "R0603(1608)"))
    )
    (comp (ref "R32")
      (value "10k")
      (footprint "eagle-import:R0603(1608)")
      (libsource (lib "eagle-import") (part "R0603(1608)"))
    )
    (comp (ref "R33")
      (value "4.7k")
      (footprint "eagle-import:R0603(1608)")
      (libsource (lib "eagle-import") (part "R0603(1608)"))
    )
    (comp (ref "R34")
      (value "4.7k")
      (footprint "eagle-import:R0603(1608)")
      (libsource (lib "eagle-import") (part "R0603(1608)"))
    )
    (comp (ref "R35")
      (value "4.7k")
      (footprint "eagle-import:R0603(1608)")
      (libsource (lib "eagle-import") (part "R0603(1608)"))
    )
    (comp (ref "R36")
      (value "470k")
      (footprint "eagle-import:R0603(1608)")
      (libsource (lib "eagle-import") (part "R0603(1608)"))
    )
    (comp (ref "R37")
      (value "1.5k")
      (footprint "eagle-import:R0603(1608)")
      (libsource (lib "eagle-import") (part "R0603(1608)"))
    )
    (comp (ref "R38")
      (value "1k")
      (footprint "eagle-import:R0603(1608)")
      (libsource (lib "eagle-import") (part "R0603(1608)"))
    )
    (comp (ref "R39")
      (value "1k")
      (footprint "eagle-import:R0603(1608)")
      (libsource (lib "eagle-import") (part "R0603(1608)"))
    )
    (comp (ref "R40")
      (value "4.7k")
      (footprint "eagle-import:R0603(1608)")
      (libsource (lib "eagle-import") (part "R0603(1608)"))
    )
    (comp (ref "R41")
      (value "0")
      (footprint "eagle-import:R0603(1608)")
      (libsource (lib "eagle-import") (part "R0603(1608)"))
    )
    (comp (ref "R42")
      (value "6.2k")
      (footprint "eagle-import:R0603(1608)")
      (libsource (lib "eagle-import") (part "R0603(1608)"))
    )
    (comp (ref "R43")
      (value "100k")
      (footprint "eagle-import:R0603(1608)")
      (libsource (lib "eagle-import") (part "R0603(1608)"))
    )
    (comp (ref "R44")
      (value "100k")
      (footprint "eagle-import:R0603(1608)")
      (libsource (lib "eagle-import") (part "R0603(1608)"))
    )
    (comp (ref "U$1")
      (value "OSSILOGORECT")
      (footprint "eagle-import:OSSILOGORECT1005")
      (libsource (lib "eagle-import") (part "OSSILOGORECT"))
    )
    (comp (ref "U9")
      (value "MSP430F1611")
      (footprint "eagle-import:PM_PAG64")
      (libsource (lib "eagle-import") (part "MSP430F1611"))
    )
    (comp (ref "U10")
      (value "MAX6369")
      (footprint "eagle-import:SOT23-8")
      (libsource (lib "eagle-import") (part "MAX6369"))
    )
    (comp (ref "U11")
      (value "TPS3838")
      (footprint "eagle-import:SOT23-5DBV")
      (libsource (lib "eagle-import") (part "TPS3838"))
    )
    (comp (ref "U12")
      (value "MAX890L")
      (footprint "eagle-import:SO8")
      (libsource (lib "eagle-import") (part "MAX890L"))
    )
    (comp (ref "U13")
      (value "MCP1700_SOT23")
      (footprint "eagle-import:SOT23")
      (libsource (lib "eagle-import") (part "MCP1700_SOT23"))
    )
    (comp (ref "X3")
      (value "M03PTH")
      (footprint "eagle-import:1X03")
      (libsource (lib "eagle-import") (part "M03PTH"))
    )
    (comp (ref "X4")
      (value "P-PAD-S")
      (footprint "eagle-import:P-PAD-S")
      (libsource (lib "eagle-import") (part "P-PAD-S"))
    )
    (comp (ref "X5")
      (value "5268-03")
      (footprint "eagle-import:5268-03")
      (libsource (lib "eagle-import") (part "5268-03"))
    )
    (comp (ref "X6")
      (value "P-PAD-S")
      (footprint "eagle-import:P-PAD-S")
      (libsource (lib "eagle-import") (part "P-PAD-S"))
    )
    (comp (ref "X7")
      (value "JTAG10PINMINI-H")
      (footprint "eagle-import:M50-3200545")
      (libsource (lib "eagle-import") (part "JTAG10PINMINI-H"))
    )
  )
  (nets
    (net (code "1") (name "3.3VCOMMS") (class "Default")
      (node (ref "C84") (pin "1") (pinfunction "1_1") (pintype "passive"))
      (node (ref "C85") (pin "1") (pinfunction "1_1") (pintype "passive"))
      (node (ref "C86") (pin "1") (pinfunction "1_1") (pintype "passive"))
      (node (ref "C90") (pin "1") (pinfunction "+_1") (pintype "passive"))
      (node (ref "C91") (pin "1") (pinfunction "1_1") (pintype "passive"))
      (node (ref "C92") (pin "P$1") (pinfunction "1_P$1") (pintype "passive"))
      (node (ref "L16") (pin "1") (pinfunction "1_1") (pintype "passive"))
      (node (ref "R12") (pin "1") (pinfunction "1_1") (pintype "passive"))
      (node (ref "R31") (pin "2") (pinfunction "2_2") (pintype "passive"))
      (node (ref "R32") (pin "2") (pinfunction "2_2") (pintype "passive"))
      (node (ref "R36") (pin "2") (pinfunction "2_2") (pintype "passive"))
      (node (ref "R44") (pin "2") (pinfunction "2_2") (pintype "passive"))
      (node (ref "U10") (pin "4") (pinfunction "P$4_4") (pintype "passive"))
      (node (ref "U10") (pin "5") (pinfunction "P$5_5") (pintype "passive"))
      (node (ref "U10") (pin "6") (pinfunction "P$6_6") (pintype "passive"))
      (node (ref "U10") (pin "8") (pinfunction "P$8_8") (pintype "power_in"))
      (node (ref "U11") (pin "5") (pinfunction "P$5_5") (pintype "power_in"))
      (node (ref "U13") (pin "2") (pinfunction "2_2") (pintype "power_in"))
      (node (ref "U9") (pin "1") (pinfunction "1_1") (pintype "power_in"))
      (node (ref "U9") (pin "64") (pinfunction "64_64") (pintype "power_in"))
      (node (ref "X7") (pin "4") (pinfunction "4_4") (pintype "bidirectional"))
    )
    (net (code "2") (name "3.3VOBC") (class "Default")
      (node (ref "X1") (pin "45") (pinfunction "45_45") (pintype "bidirectional"))
      (node (ref "X1") (pin "46") (pinfunction "46_46") (pintype "bidirectional"))
    )
    (net (code "3") (name "ANT_DEPLOY1") (class "Default")
      (node (ref "X1") (pin "19") (pinfunction "19_19") (pintype "bidirectional"))
    )
    (net (code "4") (name "ANT_DEPLOY2") (class "Default")
      (node (ref "X1") (pin "20") (pinfunction "20_20") (pintype "bidirectional"))
    )
    (net (code "5") (name "BAT_-CHRG") (class "Default")
      (node (ref "X1") (pin "42") (pinfunction "42_42") (pintype "bidirectional"))
    )
    (net (code "6") (name "BAT_-FAULT") (class "Default")
      (node (ref "X1") (pin "44") (pinfunction "44_44") (pintype "bidirectional"))
    )
    (net (code "7") (name "BAT_-ON") (class "Default")
      (node (ref "X1") (pin "38") (pinfunction "38_38") (pintype "bidirectional"))
    )
    (net (code "8") (name "BAT_TEMP") (class "Default")
      (node (ref "X1") (pin "47") (pinfunction "47_47") (pintype "bidirectional"))
    )
    (net (code "9") (name "BEACON_-FAULT") (class "Default")
      (node (ref "X1") (pin "30") (pinfunction "30_30") (pintype "bidirectional"))
    )
    (net (code "10") (name "BEACON_OFF") (class "Default")
      (node (ref "X1") (pin "24") (pinfunction "24_24") (pintype "bidirectional"))
    )
    (net (code "11") (name "BEACON_SCL") (class "Default")
      (node (ref "X1") (pin "37") (pinfunction "37_37") (pintype "bidirectional"))
    )
    (net (code "12") (name "BEACON_SDA") (class "Default")
      (node (ref "X1") (pin "39") (pinfunction "39_39") (pintype "bidirectional"))
    )
    (net (code "13") (name "BUS_CS") (class "Default")
      (node (ref "X1") (pin "27") (pinfunction "27_27") (pintype "bidirectional"))
    )
    (net (code "14") (name "COMMSRX_CE") (class "Default")
      (node (ref "U7") (pin "24") (pinfunction "P$24_24") (pintype "bidirectional"))
      (node (ref "U9") (pin "21") (pinfunction "21_21") (pintype "bidirectional"))
    )
    (net (code "15") (name "COMMSRX_CLK") (class "Default")
      (node (ref "R35") (pin "2") (pinfunction "2_2") (pintype "passive"))
      (node (ref "U7") (pin "35") (pinfunction "P$35_35") (pintype "bidirectional"))
    )
    (net (code "16") (name "COMMSRX_CLKOUT") (class "Default")
      (node (ref "U7") (pin "36") (pinfunction "P$36_36") (pintype "bidirectional"))
    )
    (net (code "17") (name "COMMSRX_CPOUT") (class "Default")
      (node (ref "C62") (pin "1") (pinfunction "1_1") (pintype "passive"))
      (node (ref "R20") (pin "2") (pinfunction "2_2") (pintype "passive"))
      (node (ref "R21") (pin "2") (pinfunction "2_2") (pintype "passive"))
      (node (ref "U7") (pin "42") (pinfunction "P$42_42") (pintype "bidirectional"))
    )
    (net (code "18") (name "COMMSRX_DATA") (class "Default")
      (node (ref "R34") (pin "2") (pinfunction "2_2") (pintype "passive"))
      (node (ref "U7") (pin "34") (pinfunction "P$34_34") (pintype "bidirectional"))
    )
    (net (code "19") (name "COMMSRX_MUXOUT") (class "Default")
      (node (ref "U7") (pin "37") (pinfunction "P$37_37") (pintype "bidirectional"))
      (node (ref "U9") (pin "13") (pinfunction "13_13") (pintype "bidirectional"))
    )
    (net (code "20") (name "COMMSRX_RFIN") (class "Default")
      (node (ref "C3") (pin "1") (pinfunction "1_1") (pintype "passive"))
      (node (ref "L1") (pin "2") (pinfunction "2_2") (pintype "passive"))
      (node (ref "U7") (pin "6") (pinfunction "P$6_6") (pintype "bidirectional"))
    )
    (net (code "21") (name "COMMSRX_RFINB") (class "Default")
      (node (ref "C1") (pin "1") (pinfunction "1_1") (pintype "passive"))
      (node (ref "L1") (pin "1") (pinfunction "1_1") (pintype "passive"))
      (node (ref "U7") (pin "7") (pinfunction "P$7_7") (pintype "bidirectional"))
    )
    (net (code "22") (name "COMMSRX_SCLK") (class "Default")
      (node (ref "U7") (pin "28") (pinfunction "P$28_28") (pintype "bidirectional"))
      (node (ref "U9") (pin "17") (pinfunction "17_17") (pintype "bidirectional"))
    )
    (net (code "23") (name "COMMSRX_SDATA") (class "Default")
      (node (ref "U7") (pin "26") (pinfunction "P$26_26") (pintype "bidirectional"))
      (node (ref "U9") (pin "19") (pinfunction "19_19") (pintype "bidirectional"))
    )
    (net (code "24") (name "COMMSRX_SLE") (class "Default")
      (node (ref "U7") (pin "25") (pinfunction "P$25_25") (pintype "bidirectional"))
      (node (ref "U9") (pin "20") (pinfunction "20_20") (pintype "bidirectional"))
    )
    (net (code "25") (name "COMMSRX_SREAD") (class "Default")
      (node (ref "U7") (pin "27") (pinfunction "P$27_27") (pintype "bidirectional"))
      (node (ref "U9") (pin "18") (pinfunction "18_18") (pintype "bidirectional"))
    )
    (net (code "26") (name "COMMSRX_SWD") (class "Default")
      (node (ref "U7") (pin "33") (pinfunction "P$33_33") (pintype "bidirectional"))
      (node (ref "U9") (pin "16") (pinfunction "16_16") (pintype "bidirectional"))
    )
    (net (code "27") (name "COMMSRX_TCXO") (class "Default")
      (node (ref "C61") (pin "2") (pinfunction "2_2") (pintype "passive"))
      (node (ref "U7") (pin "39") (pinfunction "P$39_39") (pintype "bidirectional"))
    )
    (net (code "28") (name "COMMSRX_VCOIN") (class "Default")
      (node (ref "C57") (pin "1") (pinfunction "1_1") (pintype "passive"))
      (node (ref "R20") (pin "1") (pinfunction "1_1") (pintype "passive"))
      (node (ref "U7") (pin "1") (pinfunction "P$1_1") (pintype "bidirectional"))
    )
    (net (code "29") (name "COMMSTX_CE") (class "Default")
      (node (ref "U8") (pin "24") (pinfunction "P$24_24") (pintype "bidirectional"))
      (node (ref "U9") (pin "37") (pinfunction "37_37") (pintype "bidirectional"))
    )
    (net (code "30") (name "COMMSTX_CLK") (class "Default")
      (node (ref "R28") (pin "2") (pinfunction "2_2") (pintype "passive"))
      (node (ref "U8") (pin "35") (pinfunction "P$35_35") (pintype "bidirectional"))
    )
    (net (code "31") (name "COMMSTX_CLKOUT") (class "Default")
      (node (ref "U8") (pin "36") (pinfunction "P$36_36") (pintype "bidirectional"))
    )
    (net (code "32") (name "COMMSTX_CPOUT") (class "Default")
      (node (ref "C75") (pin "1") (pinfunction "1_1") (pintype "passive"))
      (node (ref "R25") (pin "2") (pinfunction "2_2") (pintype "passive"))
      (node (ref "R26") (pin "2") (pinfunction "2_2") (pintype "passive"))
      (node (ref "U8") (pin "42") (pinfunction "P$42_42") (pintype "bidirectional"))
    )
    (net (code "33") (name "COMMSTX_DATA") (class "Default")
      (node (ref "R29") (pin "2") (pinfunction "2_2") (pintype "passive"))
      (node (ref "U8") (pin "34") (pinfunction "P$34_34") (pintype "bidirectional"))
    )
    (net (code "34") (name "COMMSTX_MUXOUT") (class "Default")
      (node (ref "U8") (pin "37") (pinfunction "P$37_37") (pintype "bidirectional"))
      (node (ref "U9") (pin "22") (pinfunction "22_22") (pintype "bidirectional"))
    )
    (net (code "35") (name "COMMSTX_RFOUT") (class "Default")
      (node (ref "C24") (pin "1") (pinfunction "1_1") (pintype "passive"))
      (node (ref "L14") (pin "1") (pinfunction "1_1") (pintype "passive"))
      (node (ref "U8") (pin "4") (pinfunction "P$4_4") (pintype "bidirectional"))
    )
    (net (code "36") (name "COMMSTX_SCLK") (class "Default")
      (node (ref "U8") (pin "28") (pinfunction "P$28_28") (pintype "bidirectional"))
      (node (ref "U9") (pin "25") (pinfunction "25_25") (pintype "bidirectional"))
    )
    (net (code "37") (name "COMMSTX_SDATA") (class "Default")
      (node (ref "U8") (pin "26") (pinfunction "P$26_26") (pintype "bidirectional"))
      (node (ref "U9") (pin "27") (pinfunction "27_27") (pintype "bidirectional"))
    )
    (net (code "38") (name "COMMSTX_SLE") (class "Default")
      (node (ref "U8") (pin "25") (pinfunction "P$25_25") (pintype "bidirectional"))
      (node (ref "U9") (pin "36") (pinfunction "36_36") (pintype "output"))
    )
    (net (code "39") (name "COMMSTX_SREAD") (class "Default")
      (node (ref "U8") (pin "27") (pinfunction "P$27_27") (pintype "bidirectional"))
      (node (ref "U9") (pin "26") (pinfunction "26_26") (pintype "bidirectional"))
    )
    (net (code "40") (name "COMMSTX_TCXO") (class "Default")
      (node (ref "C78") (pin "2") (pinfunction "2_2") (pintype "passive"))
      (node (ref "U8") (pin "39") (pinfunction "P$39_39") (pintype "bidirectional"))
    )
    (net (code "41") (name "COMMSTX_VCOIN") (class "Default")
      (node (ref "C72") (pin "1") (pinfunction "1_1") (pintype "passive"))
      (node (ref "R25") (pin "1") (pinfunction "1_1") (pintype "passive"))
      (node (ref "U8") (pin "1") (pinfunction "P$1_1") (pintype "bidirectional"))
    )
    (net (code "42") (name "COMMS_-FAULT") (class "Default")
      (node (ref "U12") (pin "8") (pinfunction "P$8_8") (pintype "output"))
      (node (ref "X1") (pin "32") (pinfunction "32_32") (pintype "bidirectional"))
    )
    (net (code "43") (name "COMMS_-RST") (class "Default")
      (node (ref "C83") (pin "1") (pinfunction "1_1") (pintype "passive"))
      (node (ref "U10") (pin "7") (pinfunction "P$7_7") (pintype "output"))
      (node (ref "U11") (pin "3") (pinfunction "P$3_3") (pintype "input"))
    )
    (net (code "44") (name "COMMS_OFF") (class "Default")
      (node (ref "C87") (pin "1") (pinfunction "1_1") (pintype "passive"))
      (node (ref "R43") (pin "2") (pinfunction "2_2") (pintype "passive"))
      (node (ref "U12") (pin "3") (pinfunction "P$3_3") (pintype "input"))
      (node (ref "X1") (pin "25") (pinfunction "25_25") (pintype "bidirectional"))
    )
    (net (code "45") (name "COMMS_SCL") (class "Default")
      (node (ref "R30") (pin "1") (pinfunction "1_1") (pintype "passive"))
      (node (ref "R32") (pin "1") (pinfunction "1_1") (pintype "passive"))
      (node (ref "X1") (pin "41") (pinfunction "41_41") (pintype "bidirectional"))
      (node (ref "X3") (pin "2") (pinfunction "2_2") (pintype "passive"))
    )
    (net (code "46") (name "COMMS_SDA") (class "Default")
      (node (ref "R27") (pin "1") (pinfunction "1_1") (pintype "passive"))
      (node (ref "R31") (pin "1") (pinfunction "1_1") (pintype "passive"))
      (node (ref "X1") (pin "43") (pinfunction "43_43") (pintype "bidirectional"))
      (node (ref "X3") (pin "1") (pinfunction "1_1") (pintype "passive"))
    )
    (net (code "47") (name "GND") (class "Default")
      (node (ref "C1") (pin "2") (pinfunction "2_2") (pintype "passive"))
      (node (ref "C11") (pin "P$2") (pinfunction "2_P$2") (pintype "passive"))
      (node (ref "C12") (pin "2") (pinfunction "2_2") (pintype "passive"))
      (node (ref "C13") (pin "2") (pinfunction "2_2") (pintype "passive"))
      (node (ref "C14") (pin "2") (pinfunction "2_2") (pintype "passive"))
      (node (ref "C16") (pin "1") (pinfunction "1_1") (pintype "passive"))
      (node (ref "C17") (pin "1") (pinfunction "1_1") (pintype "passive"))
      (node (ref "C18") (pin "2") (pinfunction "2_2") (pintype "passive"))
      (node (ref "C19") (pin "2") (pinfunction "2_2") (pintype "passive"))
      (node (ref "C2") (pin "2") (pinfunction "2_2") (pintype "passive"))
      (node (ref "C20") (pin "2") (pinfunction "2_2") (pintype "passive"))
      (node (ref "C21") (pin "2") (pinfunction "2_2") (pintype "passive"))
      (node (ref "C22") (pin "2") (pinfunction "2_2") (pintype "passive"))
      (node (ref "C23") (pin "1") (pinfunction "1_1") (pintype "passive"))
      (node (ref "C27") (pin "2") (pinfunction "2_2") (pintype "passive"))
      (node (ref "C28") (pin "1") (pinfunction "1_1") (pintype "passive"))
      (node (ref "C29") (pin "2") (pinfunction "2_2") (pintype "passive"))
      (node (ref "C30") (pin "2") (pinfunction "2_2") (pintype "passive"))
      (node (ref "C31") (pin "2") (pinfunction "2_2") (pintype "passive"))
      (node (ref "C32") (pin "1") (pinfunction "1_1") (pintype "passive"))
      (node (ref "C33") (pin "2") (pinfunction "2_2") (pintype "passive"))
      (node (ref "C34") (pin "2") (pinfunction "2_2") (pintype "passive"))
      (node (ref "C35") (pin "2") (pinfunction "2_2") (pintype "passive"))
      (node (ref "C36") (pin "1") (pinfunction "1_1") (pintype "passive"))
      (node (ref "C37") (pin "P$2") (pinfunction "2_P$2") (pintype "passive"))
      (node (ref "C39") (pin "2") (pinfunction "2_2") (pintype "passive"))
      (node (ref "C40") (pin "2") (pinfunction "2_2") (pintype "passive"))
      (node (ref "C41") (pin "P$2") (pinfunction "2_P$2") (pintype "passive"))
      (node (ref "C42") (pin "P$2") (pinfunction "2_P$2") (pintype "passive"))
      (node (ref "C43") (pin "2") (pinfunction "2_2") (pintype "passive"))
      (node (ref "C44") (pin "2") (pinfunction "2_2") (pintype "passive"))
      (node (ref "C45") (pin "P$2") (pinfunction "2_P$2") (pintype "passive"))
      (node (ref "C46") (pin "P$2") (pinfunction "2_P$2") (pintype "passive"))
      (node (ref "C47") (pin "2") (pinfunction "2_2") (pintype "passive"))
      (node (ref "C48") (pin "2") (pinfunction "2_2") (pintype "passive"))
      (node (ref "C49") (pin "2") (pinfunction "2_2") (pintype "passive"))
      (node (ref "C5") (pin "2") (pinfunction "2_2") (pintype "passive"))
      (node (ref "C50") (pin "2") (pinfunction "2_2") (pintype "passive"))
      (node (ref "C51") (pin "2") (pinfunction "2_2") (pintype "passive"))
      (node (ref "C52") (pin "2") (pinfunction "2_2") (pintype "passive"))
      (node (ref "C53") (pin "2") (pinfunction "2_2") (pintype "passive"))
      (node (ref "C56") (pin "2") (pinfunction "2_2") (pintype "passive"))
      (node (ref "C57") (pin "2") (pinfunction "2_2") (pintype "passive"))
      (node (ref "C58") (pin "2") (pinfunction "2_2") (pintype "passive"))
      (node (ref "C59") (pin "2") (pinfunction "2_2") (pintype "passive"))
      (node (ref "C6") (pin "P$2") (pinfunction "2_P$2") (pintype "passive"))
      (node (ref "C60") (pin "2") (pinfunction "2_2") (pintype "passive"))
      (node (ref "C62") (pin "2") (pinfunction "2_2") (pintype "passive"))
      (node (ref "C63") (pin "2") (pinfunction "2_2") (pintype "passive"))
      (node (ref "C64") (pin "2") (pinfunction "2_2") (pintype "passive"))
      (node (ref "C65") (pin "2") (pinfunction "2_2") (pintype "passive"))
      (node (ref "C66") (pin "2") (pinfunction "2_2") (pintype "passive"))
      (node (ref "C67") (pin "2") (pinfunction "2_2") (pintype "passive"))
      (node (ref "C69") (pin "2") (pinfunction "2_2") (pintype "passive"))
      (node (ref "C7") (pin "2") (pinfunction "2_2") (pintype "passive"))
      (node (ref "C70") (pin "2") (pinfunction "2_2") (pintype "passive"))
      (node (ref "C72") (pin "2") (pinfunction "2_2") (pintype "passive"))
      (node (ref "C73") (pin "2") (pinfunction "2_2") (pintype "passive"))
      (node (ref "C74") (pin "2") (pinfunction "2_2") (pintype "passive"))
      (node (ref "C75") (pin "2") (pinfunction "2_2") (pintype "passive"))
      (node (ref "C76") (pin "2") (pinfunction "2_2") (pintype "passive"))
      (node (ref "C77") (pin "2") (pinfunction "2_2") (pintype "passive"))
      (node (ref "C79") (pin "2") (pinfunction "2_2") (pintype "passive"))
      (node (ref "C80") (pin "2") (pinfunction "2_2") (pintype "passive"))
      (node (ref "C81") (pin "2") (pinfunction "2_2") (pintype "passive"))
      (node (ref "C82") (pin "2") (pinfunction "2_2") (pintype "passive"))
      (node (ref "C83") (pin "2") (pinfunction "2_2") (pintype "passive"))
      (node (ref "C84") (pin "2") (pinfunction "2_2") (pintype "passive"))
      (node (ref "C85") (pin "2") (pinfunction "2_2") (pintype "passive"))
      (node (ref "C86") (pin "2") (pinfunction "2_2") (pintype "passive"))
      (node (ref "C87") (pin "2") (pinfunction "2_2") (pintype "passive"))
      (node (ref "C88") (pin "2") (pinfunction "2_2") (pintype "passive"))
      (node (ref "C89") (pin "2") (pinfunction "-_2") (pintype "passive"))
      (node (ref "C91") (pin "2") (pinfunction "2_2") (pintype "passive"))
      (node (ref "C92") (pin "P$2") (pinfunction "2_P$2") (pintype "passive"))
      (node (ref "C93") (pin "2") (pinfunction "2_2") (pintype "passive"))
      (node (ref "F1") (pin "2") (pinfunction "P$2_2") (pintype "power_in"))
      (node (ref "F1") (pin "4") (pinfunction "P$4_4") (pintype "power_in"))
      (node (ref "JP2") (pin "2") (pinfunction "2_2") (pintype "passive"))
      (node (ref "L2") (pin "2") (pinfunction "2_2") (pintype "passive"))
      (node (ref "L4") (pin "2") (pinfunction "2_2") (pintype "passive"))
      (node (ref "LED1") (pin "C") (pinfunction "C_C") (pintype "passive"))
      (node (ref "LED2") (pin "C") (pinfunction "C_C") (pintype "passive"))
      (node (ref "R1") (pin "1") (pinfunction "1_1") (pintype "passive"))
      (node (ref "R11") (pin "1") (pinfunction "1_1") (pintype "passive"))
      (node (ref "R13") (pin "2") (pinfunction "2_2") (pintype "passive"))
      (node (ref "R17") (pin "1") (pinfunction "1_1") (pintype "passive"))
      (node (ref "R18") (pin "2") (pinfunction "2_2") (pintype "passive"))
      (node (ref "R19") (pin "2") (pinfunction "2_2") (pintype "passive"))
      (node (ref "R22") (pin "1") (pinfunction "1_1") (pintype "passive"))
      (node (ref "R23") (pin "1") (pinfunction "1_1") (pintype "passive"))
      (node (ref "R24") (pin "1") (pinfunction "1_1") (pintype "passive"))
      (node (ref "R4") (pin "1") (pinfunction "1_1") (pintype "passive"))
      (node (ref "R41") (pin "2") (pinfunction "2_2") (pintype "passive"))
      (node (ref "R42") (pin "1") (pinfunction "1_1") (pintype "passive"))
      (node (ref "R43") (pin "1") (pinfunction "1_1") (pintype "passive"))
      (node (ref "R7") (pin "2") (pinfunction "2_2") (pintype "passive"))
      (node (ref "R8") (pin "2") (pinfunction "2_2") (pintype "passive"))
      (node (ref "TCXO1") (pin "1") (pinfunction "P$1_1") (pintype "bidirectional"))
      (node (ref "TCXO1") (pin "2") (pinfunction "P$2_2") (pintype "bidirectional"))
      (node (ref "TCXO2") (pin "1") (pinfunction "P$1_1") (pintype "bidirectional"))
      (node (ref "TCXO2") (pin "2") (pinfunction "P$2_2") (pintype "bidirectional"))
      (node (ref "TP1") (pin "TP") (pinfunction "TP_TP") (pintype "input"))
      (node (ref "TR1") (pin "2") (pinfunction "S_2") (pintype "bidirectional"))
      (node (ref "U1") (pin "2") (pinfunction "2_2") (pintype "power_in"))
      (node (ref "U1") (pin "3") (pinfunction "3_3") (pintype "power_in"))
      (node (ref "U1") (pin "5") (pinfunction "5_5") (pintype "power_in"))
      (node (ref "U10") (pin "2") (pinfunction "P$2_2") (pintype "power_in"))
      (node (ref "U11") (pin "1") (pinfunction "P$1_1") (pintype "bidirectional"))
      (node (ref "U11") (pin "2") (pinfunction "P$2_2") (pintype "power_in"))
      (node (ref "U12") (pin "4") (pinfunction "P$4_4") (pintype "power_in"))
      (node (ref "U13") (pin "1") (pinfunction "1_1") (pintype "power_in"))
      (node (ref "U2") (pin "2") (pinfunction "P$2_2") (pintype "bidirectional"))
      (node (ref "U3") (pin "2") (pinfunction "P$2_2") (pintype "bidirectional"))
      (node (ref "U3") (pin "4") (pinfunction "P$4_4") (pintype "bidirectional"))
      (node (ref "U3") (pin "TPAD") (pinfunction "P$17_TPAD") (pintype "bidirectional"))
      (node (ref "U4") (pin "2") (pinfunction "V-_2") (pintype "power_in"))
      (node (ref "U5") (pin "8") (pinfunction "P$8_8") (pintype "power_in"))
      (node (ref "U6") (pin "4") (pinfunction "P$4_4") (pintype "power_in"))
      (node (ref "U6") (pin "PAD") (pinfunction "P$8_PAD") (pintype "power_in"))
      (node (ref "U7") (pin "12") (pinfunction "P$12_12") (pintype "bidirectional"))
      (node (ref "U7") (pin "19") (pinfunction "P$19_19") (pintype "bidirectional"))
      (node (ref "U7") (pin "22") (pinfunction "P$22_22") (pintype "bidirectional"))
      (node (ref "U7") (pin "29") (pinfunction "P$29_29") (pintype "bidirectional"))
      (node (ref "U7") (pin "45") (pinfunction "P$45_45") (pintype "bidirectional"))
      (node (ref "U7") (pin "47") (pinfunction "P$47_47") (pintype "bidirectional"))
      (node (ref "U7") (pin "5") (pinfunction "P$5_5") (pintype "bidirectional"))
      (node (ref "U7") (pin "EXP") (pinfunction "P$49_EXP") (pintype "bidirectional"))
      (node (ref "U8") (pin "12") (pinfunction "P$12_12") (pintype "bidirectional"))
      (node (ref "U8") (pin "19") (pinfunction "P$19_19") (pintype "bidirectional"))
      (node (ref "U8") (pin "22") (pinfunction "P$22_22") (pintype "bidirectional"))
      (node (ref "U8") (pin "29") (pinfunction "P$29_29") (pintype "bidirectional"))
      (node (ref "U8") (pin "45") (pinfunction "P$45_45") (pintype "bidirectional"))
      (node (ref "U8") (pin "47") (pinfunction "P$47_47") (pintype "bidirectional"))
      (node (ref "U8") (pin "5") (pinfunction "P$5_5") (pintype "bidirectional"))
      (node (ref "U8") (pin "6") (pinfunction "P$6_6") (pintype "bidirectional"))
      (node (ref "U8") (pin "7") (pinfunction "P$7_7") (pintype "bidirectional"))
      (node (ref "U8") (pin "EXP") (pinfunction "P$49_EXP") (pintype "bidirectional"))
      (node (ref "U9") (pin "53") (pinfunction "53_53") (pintype "input"))
      (node (ref "U9") (pin "62") (pinfunction "62_62") (pintype "power_in"))
      (node (ref "U9") (pin "63") (pinfunction "63_63") (pintype "power_in"))
      (node (ref "X1") (pin "1") (pinfunction "1_1") (pintype "bidirectional"))
      (node (ref "X1") (pin "2") (pinfunction "2_2") (pintype "bidirectional"))
      (node (ref "X1") (pin "51") (pinfunction "51_51") (pintype "bidirectional"))
      (node (ref "X1") (pin "52") (pinfunction "52_52") (pintype "bidirectional"))
      (node (ref "X2") (pin "2") (pinfunction "2_2") (pintype "power_in"))
      (node (ref "X2") (pin "3") (pinfunction "3_3") (pintype "power_in"))
      (node (ref "X2") (pin "4") (pinfunction "4_4") (pintype "power_in"))
      (node (ref "X2") (pin "5") (pinfunction "5_5") (pintype "power_in"))
      (node (ref "X3") (pin "3") (pinfunction "3_3") (pintype "passive"))
      (node (ref "X5") (pin "1") (pinfunction "1_1") (pintype "bidirectional"))
      (node (ref "X7") (pin "9") (pinfunction "9_9") (pintype "bidirectional"))
    )
    (net (code "48") (name "LED1") (class "Default")
      (node (ref "R39") (pin "1") (pinfunction "1_1") (pintype "passive"))
      (node (ref "U9") (pin "50") (pinfunction "50_50") (pintype "bidirectional"))
    )
    (net (code "49") (name "LED_-FAULT") (class "Default")
      (node (ref "X1") (pin "28") (pinfunction "28_28") (pintype "bidirectional"))
    )
    (net (code "50") (name "LED_OFF") (class "Default")
      (node (ref "X1") (pin "23") (pinfunction "23_23") (pintype "bidirectional"))
    )
    (net (code "51") (name "LED_SCL") (class "Default")
      (node (ref "X1") (pin "33") (pinfunction "33_33") (pintype "bidirectional"))
    )
    (net (code "52") (name "LED_SDA") (class "Default")
      (node (ref "X1") (pin "35") (pinfunction "35_35") (pintype "bidirectional"))
    )
    (net (code "53") (name "Net-(C2-Pad1)") (class "Default")
      (node (ref "C2") (pin "1") (pinfunction "1_1") (pintype "passive"))
      (node (ref "C3") (pin "2") (pinfunction "2_2") (pintype "passive"))
      (node (ref "L3") (pin "1") (pinfunction "1_1") (pintype "passive"))
    )
    (net (code "54") (name "Net-(C4-Pad1)") (class "Default")
      (node (ref "C4") (pin "1") (pinfunction "1_1") (pintype "passive"))
      (node (ref "L2") (pin "1") (pinfunction "1_1") (pintype "passive"))
      (node (ref "L3") (pin "2") (pinfunction "2_2") (pintype "passive"))
    )
    (net (code "55") (name "Net-(C4-Pad2)") (class "Default")
      (node (ref "C4") (pin "2") (pinfunction "2_2") (pintype "passive"))
      (node (ref "U1") (pin "4") (pinfunction "4_4") (pintype "output"))
    )
    (net (code "56") (name "Net-(C8-Pad1)") (class "Default")
      (node (ref "C8") (pin "1") (pinfunction "1_1") (pintype "passive"))
      (node (ref "L5") (pin "2") (pinfunction "2_2") (pintype "passive"))
    )
    (net (code "57") (name "Net-(C9-Pad1)") (class "Default")
      (node (ref "C9") (pin "1") (pinfunction "1_1") (pintype "passive"))
      (node (ref "L4") (pin "1") (pinfunction "1_1") (pintype "passive"))
      (node (ref "L6") (pin "2") (pinfunction "2_2") (pintype "passive"))
    )
    (net (code "58") (name "Net-(C10-Pad1)") (class "Default")
      (node (ref "C10") (pin "1") (pinfunction "1_1") (pintype "passive"))
      (node (ref "X2") (pin "1") (pinfunction "1_1") (pintype "bidirectional"))
    )
    (net (code "59") (name "Net-(C15-Pad2)") (class "Default")
      (node (ref "C15") (pin "2") (pinfunction "2_2") (pintype "passive"))
      (node (ref "C16") (pin "2") (pinfunction "2_2") (pintype "passive"))
      (node (ref "L8") (pin "2") (pinfunction "2_2") (pintype "passive"))
    )
    (net (code "60") (name "Net-(C17-Pad2)") (class "Default")
      (node (ref "C17") (pin "2") (pinfunction "2_2") (pintype "passive"))
      (node (ref "L10") (pin "2") (pinfunction "2_2") (pintype "passive"))
      (node (ref "L8") (pin "1") (pinfunction "1_1") (pintype "passive"))
    )
    (net (code "61") (name "Net-(C18-Pad1)") (class "Default")
      (node (ref "C18") (pin "1") (pinfunction "1_1") (pintype "passive"))
      (node (ref "C24") (pin "2") (pinfunction "2_2") (pintype "passive"))
      (node (ref "L11") (pin "1") (pinfunction "1_1") (pintype "passive"))
    )
    (net (code "62") (name "Net-(C19-Pad1)") (class "Default")
      (node (ref "C19") (pin "1") (pinfunction "1_1") (pintype "passive"))
      (node (ref "L11") (pin "2") (pinfunction "2_2") (pintype "passive"))
      (node (ref "L12") (pin "1") (pinfunction "1_1") (pintype "passive"))
    )
    (net (code "63") (name "Net-(C20-Pad1)") (class "Default")
      (node (ref "C20") (pin "1") (pinfunction "1_1") (pintype "passive"))
      (node (ref "C25") (pin "1") (pinfunction "1_1") (pintype "passive"))
      (node (ref "L12") (pin "2") (pinfunction "2_2") (pintype "passive"))
      (node (ref "R4") (pin "2") (pinfunction "2_2") (pintype "passive"))
    )
    (net (code "64") (name "Net-(C21-Pad1)") (class "Default")
      (node (ref "C21") (pin "1") (pinfunction "1_1") (pintype "passive"))
      (node (ref "C22") (pin "1") (pinfunction "1_1") (pintype "passive"))
      (node (ref "C26") (pin "1") (pinfunction "1_1") (pintype "passive"))
      (node (ref "L13") (pin "2") (pinfunction "2_2") (pintype "passive"))
    )
    (net (code "65") (name "Net-(C23-Pad2)") (class "Default")
      (node (ref "C23") (pin "2") (pinfunction "2_2") (pintype "passive"))
      (node (ref "C26") (pin "2") (pinfunction "2_2") (pintype "passive"))
      (node (ref "L10") (pin "1") (pinfunction "1_1") (pintype "passive"))
    )
    (net (code "66") (name "Net-(C38-Pad2)") (class "Default")
      (node (ref "C38") (pin "2") (pinfunction "2_2") (pintype "passive"))
      (node (ref "R6") (pin "1") (pinfunction "1_1") (pintype "passive"))
    )
    (net (code "67") (name "Net-(C41-1)") (class "Default")
      (node (ref "C41") (pin "P$1") (pinfunction "1_P$1") (pintype "passive"))
      (node (ref "C42") (pin "P$1") (pinfunction "1_P$1") (pintype "passive"))
      (node (ref "U5") (pin "11") (pinfunction "P$11_11") (pintype "power_in"))
      (node (ref "U5") (pin "14") (pinfunction "P$14_14") (pintype "power_in"))
      (node (ref "U5") (pin "15") (pinfunction "P$15_15") (pintype "power_in"))
      (node (ref "U5") (pin "2") (pinfunction "P$2_2") (pintype "power_in"))
      (node (ref "U5") (pin "3") (pinfunction "P$3_3") (pintype "power_in"))
      (node (ref "U5") (pin "6") (pinfunction "P$6_6") (pintype "power_in"))
      (node (ref "U6") (pin "1") (pinfunction "P$1_1") (pintype "power_in"))
      (node (ref "U6") (pin "2") (pinfunction "P$2_2") (pintype "input"))
    )
    (net (code "68") (name "Net-(C54-Pad2)") (class "Default")
      (node (ref "C54") (pin "2") (pinfunction "2_2") (pintype "passive"))
      (node (ref "R17") (pin "2") (pinfunction "2_2") (pintype "passive"))
    )
    (net (code "69") (name "Net-(C58-Pad1)") (class "Default")
      (node (ref "C58") (pin "1") (pinfunction "1_1") (pintype "passive"))
      (node (ref "R21") (pin "1") (pinfunction "1_1") (pintype "passive"))
    )
    (net (code "70") (name "Net-(C68-Pad2)") (class "Default")
      (node (ref "C68") (pin "2") (pinfunction "2_2") (pintype "passive"))
      (node (ref "R23") (pin "2") (pinfunction "2_2") (pintype "passive"))
    )
    (net (code "71") (name "Net-(C73-Pad1)") (class "Default")
      (node (ref "C73") (pin "1") (pinfunction "1_1") (pintype "passive"))
      (node (ref "R26") (pin "1") (pinfunction "1_1") (pintype "passive"))
    )
    (net (code "72") (name "Net-(C80-Pad1)") (class "Default")
      (node (ref "C80") (pin "1") (pinfunction "1_1") (pintype "passive"))
      (node (ref "Q1") (pin "2") (pinfunction "2_2") (pintype "passive"))
      (node (ref "U9") (pin "9") (pinfunction "9_9") (pintype "bidirectional"))
    )
    (net (code "73") (name "Net-(C81-Pad1)") (class "Default")
      (node (ref "C81") (pin "1") (pinfunction "1_1") (pintype "passive"))
      (node (ref "Q1") (pin "1") (pinfunction "1_1") (pintype "passive"))
      (node (ref "U9") (pin "8") (pinfunction "8_8") (pintype "input"))
    )
    (net (code "74") (name "Net-(C82-Pad1)") (class "Default")
      (node (ref "C82") (pin "1") (pinfunction "1_1") (pintype "passive"))
      (node (ref "U9") (pin "7") (pinfunction "7_7") (pintype "output"))
    )
    (net (code "75") (name "Net-(C89-+)") (class "Default")
      (node (ref "C88") (pin "1") (pinfunction "1_1") (pintype "passive"))
      (node (ref "C89") (pin "1") (pinfunction "+_1") (pintype "passive"))
      (node (ref "U12") (pin "6") (pinfunction "P$6_6") (pintype "output"))
      (node (ref "U12") (pin "7") (pinfunction "P$7_7") (pintype "output"))
      (node (ref "U13") (pin "3") (pinfunction "3_3") (pintype "power_in"))
    )
    (net (code "76") (name "Net-(C90--)") (class "Default")
      (node (ref "C90") (pin "2") (pinfunction "-_2") (pintype "passive"))
      (node (ref "R41") (pin "1") (pinfunction "1_1") (pintype "passive"))
    )
    (net (code "77") (name "Net-(F1-P$1)") (class "Default")
      (node (ref "C5") (pin "1") (pinfunction "1_1") (pintype "passive"))
      (node (ref "F1") (pin "1") (pinfunction "P$1_1") (pintype "input"))
      (node (ref "L6") (pin "1") (pinfunction "1_1") (pintype "passive"))
    )
    (net (code "78") (name "Net-(F1-P$3)") (class "Default")
      (node (ref "C8") (pin "2") (pinfunction "2_2") (pintype "passive"))
      (node (ref "F1") (pin "3") (pinfunction "P$3_3") (pintype "output"))
    )
    (net (code "79") (name "Net-(JP2-Pad1)") (class "Default")
      (node (ref "JP2") (pin "1") (pinfunction "1_1") (pintype "passive"))
      (node (ref "LED2") (pin "A") (pinfunction "A_A") (pintype "passive"))
      (node (ref "R39") (pin "2") (pinfunction "2_2") (pintype "passive"))
    )
    (net (code "80") (name "Net-(L5-Pad1)") (class "Default")
      (node (ref "L5") (pin "1") (pinfunction "1_1") (pintype "passive"))
      (node (ref "U1") (pin "1") (pinfunction "1_1") (pintype "bidirectional"))
    )
    (net (code "81") (name "Net-(L7-2)") (class "Default")
      (node (ref "C14") (pin "1") (pinfunction "1_1") (pintype "passive"))
      (node (ref "L7") (pin "P$2") (pinfunction "2_P$2") (pintype "passive"))
      (node (ref "L9") (pin "1") (pinfunction "1_1") (pintype "passive"))
    )
    (net (code "82") (name "Net-(L15-1)") (class "Default")
      (node (ref "L13") (pin "1") (pinfunction "1_1") (pintype "passive"))
      (node (ref "L15") (pin "P$1") (pinfunction "1_P$1") (pintype "passive"))
      (node (ref "U3") (pin "10") (pinfunction "P$10_10") (pintype "bidirectional"))
      (node (ref "U3") (pin "11") (pinfunction "P$11_11") (pintype "bidirectional"))
      (node (ref "U3") (pin "12") (pinfunction "P$12_12") (pintype "bidirectional"))
      (node (ref "U3") (pin "9") (pinfunction "P$9_9") (pintype "bidirectional"))
    )
    (net (code "83") (name "Net-(LED1-PadA)") (class "Default")
      (node (ref "LED1") (pin "A") (pinfunction "A_A") (pintype "passive"))
      (node (ref "R38") (pin "2") (pinfunction "2_2") (pintype "passive"))
    )
    (net (code "84") (name "Net-(R27-Pad2)") (class "Default")
      (node (ref "R27") (pin "2") (pinfunction "2_2") (pintype "passive"))
      (node (ref "U9") (pin "29") (pinfunction "29_29") (pintype "bidirectional"))
    )
    (net (code "85") (name "Net-(R28-Pad1)") (class "Default")
      (node (ref "R28") (pin "1") (pinfunction "1_1") (pintype "passive"))
      (node (ref "U9") (pin "23") (pinfunction "23_23") (pintype "bidirectional"))
    )
    (net (code "86") (name "Net-(R29-Pad1)") (class "Default")
      (node (ref "R29") (pin "1") (pinfunction "1_1") (pintype "passive"))
      (node (ref "U9") (pin "24") (pinfunction "24_24") (pintype "bidirectional"))
    )
    (net (code "87") (name "Net-(R30-Pad2)") (class "Default")
      (node (ref "R30") (pin "2") (pinfunction "2_2") (pintype "passive"))
      (node (ref "U9") (pin "31") (pinfunction "31_31") (pintype "bidirectional"))
    )
    (net (code "88") (name "Net-(R34-Pad1)") (class "Default")
      (node (ref "R34") (pin "1") (pinfunction "1_1") (pintype "passive"))
      (node (ref "U9") (pin "15") (pinfunction "15_15") (pintype "bidirectional"))
    )
    (net (code "89") (name "Net-(R35-Pad1)") (class "Default")
      (node (ref "R35") (pin "1") (pinfunction "1_1") (pintype "passive"))
      (node (ref "U9") (pin "14") (pinfunction "14_14") (pintype "bidirectional"))
    )
    (net (code "90") (name "Net-(R38-Pad1)") (class "Default")
      (node (ref "R38") (pin "1") (pinfunction "1_1") (pintype "passive"))
      (node (ref "U9") (pin "49") (pinfunction "49_49") (pintype "bidirectional"))
    )
    (net (code "91") (name "Net-(R40-Pad1)") (class "Default")
      (node (ref "R40") (pin "1") (pinfunction "1_1") (pintype "passive"))
      (node (ref "X7") (pin "10") (pinfunction "10_10") (pintype "bidirectional"))
    )
    (net (code "92") (name "Net-(TCXO1-P$3)") (class "Default")
      (node (ref "C61") (pin "1") (pinfunction "1_1") (pintype "passive"))
      (node (ref "TCXO1") (pin "3") (pinfunction "P$3_3") (pintype "bidirectional"))
    )
    (net (code "93") (name "Net-(TCXO2-P$3)") (class "Default")
      (node (ref "C78") (pin "1") (pinfunction "1_1") (pintype "passive"))
      (node (ref "TCXO2") (pin "3") (pinfunction "P$3_3") (pintype "bidirectional"))
    )
    (net (code "94") (name "Net-(TR1-D)") (class "Default")
      (node (ref "C40") (pin "1") (pinfunction "1_1") (pintype "passive"))
      (node (ref "R15") (pin "1") (pinfunction "1_1") (pintype "passive"))
      (node (ref "TR1") (pin "3") (pinfunction "D_3") (pintype "bidirectional"))
      (node (ref "U5") (pin "7") (pinfunction "P$7_7") (pintype "input"))
    )
    (net (code "95") (name "Net-(TR1-G)") (class "Default")
      (node (ref "R10") (pin "1") (pinfunction "1_1") (pintype "passive"))
      (node (ref "TR1") (pin "1") (pinfunction "G_1") (pintype "bidirectional"))
    )
    (net (code "96") (name "Net-(U2-P$1)") (class "Default")
      (node (ref "C15") (pin "1") (pinfunction "1_1") (pintype "passive"))
      (node (ref "U2") (pin "1") (pinfunction "P$1_1") (pintype "bidirectional"))
    )
    (net (code "97") (name "Net-(U2-P$3)") (class "Default")
      (node (ref "C9") (pin "2") (pinfunction "2_2") (pintype "passive"))
      (node (ref "U2") (pin "3") (pinfunction "P$3_3") (pintype "bidirectional"))
    )
    (net (code "98") (name "Net-(U2-P$4)") (class "Default")
      (node (ref "R2") (pin "2") (pinfunction "2_2") (pintype "passive"))
      (node (ref "U2") (pin "4") (pinfunction "P$4_4") (pintype "bidirectional"))
    )
    (net (code "99") (name "Net-(U2-P$5)") (class "Default")
      (node (ref "C10") (pin "2") (pinfunction "2_2") (pintype "passive"))
      (node (ref "U2") (pin "5") (pinfunction "P$5_5") (pintype "bidirectional"))
    )
    (net (code "100") (name "Net-(U2-P$6)") (class "Default")
      (node (ref "R3") (pin "1") (pinfunction "1_1") (pintype "passive"))
      (node (ref "U2") (pin "6") (pinfunction "P$6_6") (pintype "bidirectional"))
    )
    (net (code "101") (name "Net-(U3-P$1)") (class "Default")
      (node (ref "R5") (pin "1") (pinfunction "1_1") (pintype "passive"))
      (node (ref "U3") (pin "1") (pinfunction "P$1_1") (pintype "bidirectional"))
    )
    (net (code "102") (name "Net-(U3-P$3)") (class "Default")
      (node (ref "C25") (pin "2") (pinfunction "2_2") (pintype "passive"))
      (node (ref "U3") (pin "3") (pinfunction "P$3_3") (pintype "bidirectional"))
    )
    (net (code "103") (name "Net-(U3-P$5)") (class "Default")
      (node (ref "L9") (pin "2") (pinfunction "2_2") (pintype "passive"))
      (node (ref "U3") (pin "5") (pinfunction "P$5_5") (pintype "bidirectional"))
      (node (ref "U3") (pin "6") (pinfunction "P$6_6") (pintype "bidirectional"))
    )
    (net (code "104") (name "Net-(U4-+IN)") (class "Default")
      (node (ref "C39") (pin "1") (pinfunction "1_1") (pintype "passive"))
      (node (ref "R14") (pin "2") (pinfunction "2_2") (pintype "passive"))
      (node (ref "U4") (pin "3") (pinfunction "+IN_3") (pintype "input"))
    )
    (net (code "105") (name "Net-(U4-OUT)") (class "Default")
      (node (ref "JP1") (pin "2") (pinfunction "2_2") (pintype "passive"))
      (node (ref "U4") (pin "1") (pinfunction "OUT_1") (pintype "output"))
    )
    (net (code "106") (name "Net-(U5-P$9)") (class "Default")
      (node (ref "R11") (pin "2") (pinfunction "2_2") (pintype "passive"))
      (node (ref "U5") (pin "9") (pinfunction "P$9_9") (pintype "passive"))
    )
    (net (code "107") (name "Net-(U6-P$3)") (class "Default")
      (node (ref "C43") (pin "1") (pinfunction "1_1") (pintype "passive"))
      (node (ref "U6") (pin "3") (pinfunction "P$3_3") (pintype "passive"))
    )
    (net (code "108") (name "Net-(U6-P$5)") (class "Default")
      (node (ref "R6") (pin "2") (pinfunction "2_2") (pintype "passive"))
      (node (ref "R8") (pin "1") (pinfunction "1_1") (pintype "passive"))
      (node (ref "R9") (pin "2") (pinfunction "2_2") (pintype "passive"))
      (node (ref "U6") (pin "5") (pinfunction "P$5_5") (pintype "input"))
    )
    (net (code "109") (name "Net-(U7-P$2)") (class "Default")
      (node (ref "C54") (pin "1") (pinfunction "1_1") (pintype "passive"))
      (node (ref "C55") (pin "2") (pinfunction "2_2") (pintype "passive"))
      (node (ref "U7") (pin "2") (pinfunction "P$2_2") (pintype "bidirectional"))
    )
    (net (code "110") (name "Net-(U7-P$8)") (class "Default")
      (node (ref "R19") (pin "1") (pinfunction "1_1") (pintype "passive"))
      (node (ref "U7") (pin "8") (pinfunction "P$8_8") (pintype "bidirectional"))
    )
    (net (code "111") (name "Net-(U7-P$10)") (class "Default")
      (node (ref "R18") (pin "1") (pinfunction "1_1") (pintype "passive"))
      (node (ref "U7") (pin "10") (pinfunction "P$10_10") (pintype "bidirectional"))
    )
    (net (code "112") (name "Net-(U7-P$11)") (class "Default")
      (node (ref "C49") (pin "1") (pinfunction "1_1") (pintype "passive"))
      (node (ref "U7") (pin "11") (pinfunction "P$11_11") (pintype "bidirectional"))
    )
    (net (code "113") (name "Net-(U7-P$31)") (class "Default")
      (node (ref "C50") (pin "1") (pinfunction "1_1") (pintype "passive"))
      (node (ref "U7") (pin "31") (pinfunction "P$31_31") (pintype "bidirectional"))
    )
    (net (code "114") (name "Net-(U7-P$41)") (class "Default")
      (node (ref "C60") (pin "1") (pinfunction "1_1") (pintype "passive"))
      (node (ref "U7") (pin "41") (pinfunction "P$41_41") (pintype "bidirectional"))
    )
    (net (code "115") (name "Net-(U7-P$48)") (class "Default")
      (node (ref "C55") (pin "1") (pinfunction "1_1") (pintype "passive"))
      (node (ref "U7") (pin "48") (pinfunction "P$48_48") (pintype "bidirectional"))
    )
    (net (code "116") (name "Net-(U8-P$2)") (class "Default")
      (node (ref "C68") (pin "1") (pinfunction "1_1") (pintype "passive"))
      (node (ref "C71") (pin "2") (pinfunction "2_2") (pintype "passive"))
      (node (ref "U8") (pin "2") (pinfunction "P$2_2") (pintype "bidirectional"))
    )
    (net (code "117") (name "Net-(U8-P$8)") (class "Default")
      (node (ref "R24") (pin "2") (pinfunction "2_2") (pintype "passive"))
      (node (ref "U8") (pin "8") (pinfunction "P$8_8") (pintype "bidirectional"))
    )
    (net (code "118") (name "Net-(U8-P$10)") (class "Default")
      (node (ref "R22") (pin "2") (pinfunction "2_2") (pintype "passive"))
      (node (ref "U8") (pin "10") (pinfunction "P$10_10") (pintype "bidirectional"))
    )
    (net (code "119") (name "Net-(U8-P$11)") (class "Default")
      (node (ref "C65") (pin "1") (pinfunction "1_1") (pintype "passive"))
      (node (ref "U8") (pin "11") (pinfunction "P$11_11") (pintype "bidirectional"))
    )
    (net (code "120") (name "Net-(U8-P$31)") (class "Default")
      (node (ref "C66") (pin "1") (pinfunction "1_1") (pintype "passive"))
      (node (ref "U8") (pin "31") (pinfunction "P$31_31") (pintype "bidirectional"))
    )
    (net (code "121") (name "Net-(U8-P$41)") (class "Default")
      (node (ref "C77") (pin "1") (pinfunction "1_1") (pintype "passive"))
      (node (ref "U8") (pin "41") (pinfunction "P$41_41") (pintype "bidirectional"))
    )
    (net (code "122") (name "Net-(U8-P$48)") (class "Default")
      (node (ref "C71") (pin "1") (pinfunction "1_1") (pintype "passive"))
      (node (ref "U8") (pin "48") (pinfunction "P$48_48") (pintype "bidirectional"))
    )
    (net (code "123") (name "Net-(U9-Pad34)") (class "Default")
      (node (ref "U9") (pin "34") (pinfunction "34_34") (pintype "bidirectional"))
      (node (ref "X5") (pin "2") (pinfunction "2_2") (pintype "bidirectional"))
    )
    (net (code "124") (name "Net-(U9-Pad35)") (class "Default")
      (node (ref "U9") (pin "35") (pinfunction "35_35") (pintype "bidirectional"))
      (node (ref "X5") (pin "3") (pinfunction "3_3") (pintype "bidirectional"))
    )
    (net (code "125") (name "Net-(U9-Pad54)") (class "Default")
      (node (ref "U9") (pin "54") (pinfunction "54_54") (pintype "bidirectional"))
      (node (ref "X7") (pin "1") (pinfunction "1_1") (pintype "bidirectional"))
    )
    (net (code "126") (name "Net-(U9-Pad55)") (class "Default")
      (node (ref "U9") (pin "55") (pinfunction "55_55") (pintype "input"))
      (node (ref "X7") (pin "3") (pinfunction "3_3") (pintype "bidirectional"))
    )
    (net (code "127") (name "Net-(U9-Pad56)") (class "Default")
      (node (ref "U9") (pin "56") (pinfunction "56_56") (pintype "input"))
      (node (ref "X7") (pin "5") (pinfunction "5_5") (pintype "bidirectional"))
    )
    (net (code "128") (name "Net-(U9-Pad57)") (class "Default")
      (node (ref "U9") (pin "57") (pinfunction "57_57") (pintype "input"))
      (node (ref "X7") (pin "7") (pinfunction "7_7") (pintype "bidirectional"))
    )
    (net (code "129") (name "Net-(U10-P$1)") (class "Default")
      (node (ref "U10") (pin "1") (pinfunction "P$1_1") (pintype "input"))
      (node (ref "U9") (pin "42") (pinfunction "42_42") (pintype "bidirectional"))
    )
    (net (code "130") (name "Net-(U12-P$5)") (class "Default")
      (node (ref "R42") (pin "2") (pinfunction "2_2") (pintype "passive"))
      (node (ref "U12") (pin "5") (pinfunction "P$5_5") (pintype "passive"))
    )
    (net (code "131") (name "Net-(X4-P$1)") (class "Default")
      (node (ref "U9") (pin "32") (pinfunction "32_32") (pintype "bidirectional"))
      (node (ref "X4") (pin "1") (pinfunction "P$1_1") (pintype "bidirectional"))
    )
    (net (code "132") (name "Net-(X6-P$1)") (class "Default")
      (node (ref "U9") (pin "33") (pinfunction "33_33") (pintype "bidirectional"))
      (node (ref "X6") (pin "1") (pinfunction "P$1_1") (pintype "bidirectional"))
    )
    (net (code "133") (name "OBC_-FAULT") (class "Default")
      (node (ref "R33") (pin "2") (pinfunction "2_2") (pintype "passive"))
      (node (ref "R36") (pin "1") (pinfunction "1_1") (pintype "passive"))
      (node (ref "X1") (pin "34") (pinfunction "34_34") (pintype "bidirectional"))
    )
    (net (code "134") (name "OBC_-FAULT_IN") (class "Default")
      (node (ref "R33") (pin "1") (pinfunction "1_1") (pintype "passive"))
      (node (ref "U9") (pin "12") (pinfunction "12_12") (pintype "bidirectional"))
    )
    (net (code "135") (name "OBC_OFF") (class "Default")
      (node (ref "R37") (pin "2") (pinfunction "2_2") (pintype "passive"))
      (node (ref "X1") (pin "26") (pinfunction "26_26") (pintype "bidirectional"))
    )
    (net (code "136") (name "OBC_OFF_OUT") (class "Default")
      (node (ref "R37") (pin "1") (pinfunction "1_1") (pintype "passive"))
      (node (ref "U9") (pin "2") (pinfunction "2_2") (pintype "bidirectional"))
    )
    (net (code "137") (name "PANELTEMP_SCL") (class "Default")
      (node (ref "X1") (pin "29") (pinfunction "29_29") (pintype "bidirectional"))
    )
    (net (code "138") (name "PANELTEMP_SDA") (class "Default")
      (node (ref "X1") (pin "31") (pinfunction "31_31") (pintype "bidirectional"))
    )
    (net (code "139") (name "PA_-FAULT") (class "Default")
      (node (ref "R12") (pin "2") (pinfunction "2_2") (pintype "passive"))
      (node (ref "U5") (pin "10") (pinfunction "P$10_10") (pintype "output"))
    )
    (net (code "140") (name "PA_BIAS") (class "Default")
      (node (ref "R13") (pin "1") (pinfunction "1_1") (pintype "passive"))
      (node (ref "R14") (pin "1") (pinfunction "1_1") (pintype "passive"))
      (node (ref "R16") (pin "2") (pinfunction "2_2") (pintype "passive"))
      (node (ref "U9") (pin "5") (pinfunction "5_5") (pintype "bidirectional"))
    )
    (net (code "141") (name "PA_ON") (class "Default")
      (node (ref "R10") (pin "2") (pinfunction "2_2") (pintype "passive"))
      (node (ref "R7") (pin "1") (pinfunction "1_1") (pintype "passive"))
      (node (ref "U9") (pin "40") (pinfunction "40_40") (pintype "input"))
    )
    (net (code "142") (name "RX_ON") (class "Default")
      (node (ref "U9") (pin "39") (pinfunction "39_39") (pintype "bidirectional"))
    )
    (net (code "143") (name "SCCHG_EN") (class "Default")
      (node (ref "X1") (pin "21") (pinfunction "21_21") (pintype "bidirectional"))
    )
    (net (code "144") (name "SCOUT_-PG") (class "Default")
      (node (ref "X1") (pin "50") (pinfunction "50_50") (pintype "bidirectional"))
    )
    (net (code "145") (name "SCOUT_EN") (class "Default")
      (node (ref "X1") (pin "22") (pinfunction "22_22") (pintype "bidirectional"))
    )
    (net (code "146") (name "SC_-ON") (class "Default")
      (node (ref "X1") (pin "40") (pinfunction "40_40") (pintype "bidirectional"))
    )
    (net (code "147") (name "SC_-PFO") (class "Default")
      (node (ref "X1") (pin "48") (pinfunction "48_48") (pintype "bidirectional"))
    )
    (net (code "148") (name "SOLAR_-ON") (class "Default")
      (node (ref "X1") (pin "36") (pinfunction "36_36") (pintype "bidirectional"))
    )
    (net (code "149") (name "SOLAR_CS1") (class "Default")
      (node (ref "X1") (pin "15") (pinfunction "15_15") (pintype "bidirectional"))
    )
    (net (code "150") (name "SOLAR_CS2") (class "Default")
      (node (ref "X1") (pin "14") (pinfunction "14_14") (pintype "bidirectional"))
    )
    (net (code "151") (name "SOLAR_CS3") (class "Default")
      (node (ref "X1") (pin "17") (pinfunction "17_17") (pintype "bidirectional"))
    )
    (net (code "152") (name "SOLAR_CS4") (class "Default")
      (node (ref "X1") (pin "16") (pinfunction "16_16") (pintype "bidirectional"))
    )
    (net (code "153") (name "SOLAR_CS5") (class "Default")
      (node (ref "X1") (pin "18") (pinfunction "18_18") (pintype "bidirectional"))
    )
    (net (code "154") (name "STRUT_GND") (class "Default")
      (node (ref "H4") (pin "B3,2") (pinfunction "MOUNT_B3,2") (pintype "passive"))
    )
    (net (code "155") (name "SUPERCAP_TEMP") (class "Default")
      (node (ref "X1") (pin "49") (pinfunction "49_49") (pintype "bidirectional"))
    )
    (net (code "156") (name "TX_ON") (class "Default")
      (node (ref "R1") (pin "2") (pinfunction "2_2") (pintype "passive"))
      (node (ref "R2") (pin "1") (pinfunction "1_1") (pintype "passive"))
      (node (ref "U9") (pin "38") (pinfunction "38_38") (pintype "bidirectional"))
    )
    (net (code "157") (name "VAPC") (class "Default")
      (node (ref "C28") (pin "2") (pinfunction "2_2") (pintype "passive"))
      (node (ref "C32") (pin "2") (pinfunction "2_2") (pintype "passive"))
      (node (ref "JP1") (pin "1") (pinfunction "1_1") (pintype "passive"))
      (node (ref "U3") (pin "15") (pinfunction "P$15_15") (pintype "bidirectional"))
      (node (ref "U3") (pin "16") (pinfunction "P$16_16") (pintype "bidirectional"))
    )
    (net (code "158") (name "VBAT") (class "Default")
      (node (ref "X1") (pin "11") (pinfunction "11_11") (pintype "bidirectional"))
      (node (ref "X1") (pin "12") (pinfunction "12_12") (pintype "bidirectional"))
    )
    (net (code "159") (name "VBUS") (class "Default")
      (node (ref "R15") (pin "2") (pinfunction "2_2") (pintype "passive"))
      (node (ref "U12") (pin "1") (pinfunction "P$1_1") (pintype "input"))
      (node (ref "U12") (pin "2") (pinfunction "P$2_2") (pintype "input"))
      (node (ref "U5") (pin "1") (pinfunction "P$1_1") (pintype "power_in"))
      (node (ref "U5") (pin "12") (pinfunction "P$12_12") (pintype "power_in"))
      (node (ref "U5") (pin "13") (pinfunction "P$13_13") (pintype "power_in"))
      (node (ref "U5") (pin "16") (pinfunction "P$16_16") (pintype "power_in"))
      (node (ref "U5") (pin "4") (pinfunction "P$4_4") (pintype "power_in"))
      (node (ref "U5") (pin "5") (pinfunction "P$5_5") (pintype "power_in"))
      (node (ref "X1") (pin "10") (pinfunction "10_10") (pintype "bidirectional"))
      (node (ref "X1") (pin "7") (pinfunction "7_7") (pintype "bidirectional"))
      (node (ref "X1") (pin "8") (pinfunction "8_8") (pintype "bidirectional"))
      (node (ref "X1") (pin "9") (pinfunction "9_9") (pintype "bidirectional"))
    )
    (net (code "160") (name "VCCRF") (class "Default")
      (node (ref "C29") (pin "1") (pinfunction "1_1") (pintype "passive"))
      (node (ref "C34") (pin "1") (pinfunction "1_1") (pintype "passive"))
      (node (ref "C48") (pin "1") (pinfunction "1_1") (pintype "passive"))
      (node (ref "C51") (pin "1") (pinfunction "1_1") (pintype "passive"))
      (node (ref "C52") (pin "1") (pinfunction "1_1") (pintype "passive"))
      (node (ref "C53") (pin "1") (pinfunction "1_1") (pintype "passive"))
      (node (ref "C56") (pin "1") (pinfunction "1_1") (pintype "passive"))
      (node (ref "C59") (pin "1") (pinfunction "1_1") (pintype "passive"))
      (node (ref "C6") (pin "P$1") (pinfunction "1_P$1") (pintype "passive"))
      (node (ref "C63") (pin "1") (pinfunction "1_1") (pintype "passive"))
      (node (ref "C64") (pin "1") (pinfunction "1_1") (pintype "passive"))
      (node (ref "C67") (pin "1") (pinfunction "1_1") (pintype "passive"))
      (node (ref "C69") (pin "1") (pinfunction "1_1") (pintype "passive"))
      (node (ref "C7") (pin "1") (pinfunction "1_1") (pintype "passive"))
      (node (ref "C70") (pin "1") (pinfunction "1_1") (pintype "passive"))
      (node (ref "C74") (pin "1") (pinfunction "1_1") (pintype "passive"))
      (node (ref "C76") (pin "1") (pinfunction "1_1") (pintype "passive"))
      (node (ref "C79") (pin "1") (pinfunction "1_1") (pintype "passive"))
      (node (ref "C93") (pin "1") (pinfunction "1_1") (pintype "passive"))
      (node (ref "L14") (pin "2") (pinfunction "2_2") (pintype "passive"))
      (node (ref "L16") (pin "2") (pinfunction "2_2") (pintype "passive"))
      (node (ref "R3") (pin "2") (pinfunction "2_2") (pintype "passive"))
      (node (ref "TCXO1") (pin "4") (pinfunction "P$4_4") (pintype "bidirectional"))
      (node (ref "TCXO2") (pin "4") (pinfunction "P$4_4") (pintype "bidirectional"))
      (node (ref "U1") (pin "6") (pinfunction "6_6") (pintype "power_in"))
      (node (ref "U7") (pin "3") (pinfunction "P$3_3") (pintype "bidirectional"))
      (node (ref "U7") (pin "32") (pinfunction "P$32_32") (pintype "bidirectional"))
      (node (ref "U7") (pin "40") (pinfunction "P$40_40") (pintype "bidirectional"))
      (node (ref "U7") (pin "43") (pinfunction "P$43_43") (pintype "bidirectional"))
      (node (ref "U7") (pin "9") (pinfunction "P$9_9") (pintype "bidirectional"))
      (node (ref "U8") (pin "3") (pinfunction "P$3_3") (pintype "bidirectional"))
      (node (ref "U8") (pin "32") (pinfunction "P$32_32") (pintype "bidirectional"))
      (node (ref "U8") (pin "40") (pinfunction "P$40_40") (pintype "bidirectional"))
      (node (ref "U8") (pin "43") (pinfunction "P$43_43") (pintype "bidirectional"))
      (node (ref "U8") (pin "9") (pinfunction "P$9_9") (pintype "bidirectional"))
    )
    (net (code "161") (name "VCOMMS_PA") (class "Default")
      (node (ref "C11") (pin "P$1") (pinfunction "1_P$1") (pintype "passive"))
      (node (ref "C12") (pin "1") (pinfunction "1_1") (pintype "passive"))
      (node (ref "C13") (pin "1") (pinfunction "1_1") (pintype "passive"))
      (node (ref "C27") (pin "1") (pinfunction "1_1") (pintype "passive"))
      (node (ref "C30") (pin "1") (pinfunction "1_1") (pintype "passive"))
      (node (ref "C31") (pin "1") (pinfunction "1_1") (pintype "passive"))
      (node (ref "C33") (pin "1") (pinfunction "1_1") (pintype "passive"))
      (node (ref "C35") (pin "1") (pinfunction "1_1") (pintype "passive"))
      (node (ref "C36") (pin "2") (pinfunction "2_2") (pintype "passive"))
      (node (ref "C37") (pin "P$1") (pinfunction "1_P$1") (pintype "passive"))
      (node (ref "C38") (pin "1") (pinfunction "1_1") (pintype "passive"))
      (node (ref "C44") (pin "1") (pinfunction "1_1") (pintype "passive"))
      (node (ref "C45") (pin "P$1") (pinfunction "1_P$1") (pintype "passive"))
      (node (ref "C46") (pin "P$1") (pinfunction "1_P$1") (pintype "passive"))
      (node (ref "C47") (pin "1") (pinfunction "1_1") (pintype "passive"))
      (node (ref "L15") (pin "P$2") (pinfunction "2_P$2") (pintype "passive"))
      (node (ref "L7") (pin "P$1") (pinfunction "1_P$1") (pintype "passive"))
      (node (ref "R16") (pin "1") (pinfunction "1_1") (pintype "passive"))
      (node (ref "R5") (pin "2") (pinfunction "2_2") (pintype "passive"))
      (node (ref "R9") (pin "1") (pinfunction "1_1") (pintype "passive"))
      (node (ref "U3") (pin "14") (pinfunction "P$14_14") (pintype "bidirectional"))
      (node (ref "U4") (pin "5") (pinfunction "V+_5") (pintype "power_in"))
      (node (ref "U6") (pin "6") (pinfunction "P$6_6") (pintype "power_in"))
      (node (ref "U6") (pin "7") (pinfunction "P$7_7") (pintype "power_in"))
    )
    (net (code "162") (name "VSOLAR") (class "Default")
      (node (ref "X1") (pin "3") (pinfunction "3_3") (pintype "bidirectional"))
      (node (ref "X1") (pin "4") (pinfunction "4_4") (pintype "bidirectional"))
      (node (ref "X1") (pin "5") (pinfunction "5_5") (pintype "bidirectional"))
      (node (ref "X1") (pin "6") (pinfunction "6_6") (pintype "bidirectional"))
    )
    (net (code "163") (name "VSUPERCAP") (class "Default")
      (node (ref "X1") (pin "13") (pinfunction "13_13") (pintype "bidirectional"))
    )
    (net (code "164") (name "unconnected-(H1-MOUNT-PadB3,2)") (class "Default")
      (node (ref "H1") (pin "B3,2") (pinfunction "MOUNT_B3,2") (pintype "passive"))
    )
    (net (code "165") (name "unconnected-(H2-MOUNT-PadB3,2)") (class "Default")
      (node (ref "H2") (pin "B3,2") (pinfunction "MOUNT_B3,2") (pintype "passive"))
    )
    (net (code "166") (name "unconnected-(H3-MOUNT-PadB3,2)") (class "Default")
      (node (ref "H3") (pin "B3,2") (pinfunction "MOUNT_B3,2") (pintype "passive"))
    )
    (net (code "167") (name "unconnected-(U3-P$7-Pad7)") (class "Default")
      (node (ref "U3") (pin "7") (pinfunction "P$7_7") (pintype "bidirectional"))
    )
    (net (code "168") (name "unconnected-(U3-P$8-Pad8)") (class "Default")
      (node (ref "U3") (pin "8") (pinfunction "P$8_8") (pintype "bidirectional"))
    )
    (net (code "169") (name "unconnected-(U3-P$13-Pad13)") (class "Default")
      (node (ref "U3") (pin "13") (pinfunction "P$13_13") (pintype "bidirectional"))
    )
    (net (code "170") (name "unconnected-(U4--IN-Pad4)") (class "Default")
      (node (ref "U4") (pin "4") (pinfunction "-IN_4") (pintype "input"))
    )
    (net (code "171") (name "unconnected-(U7-P$4-Pad4)") (class "Default")
      (node (ref "U7") (pin "4") (pinfunction "P$4_4") (pintype "bidirectional"))
    )
    (net (code "172") (name "unconnected-(U7-P$13-Pad13)") (class "Default")
      (node (ref "U7") (pin "13") (pinfunction "P$13_13") (pintype "bidirectional"))
    )
    (net (code "173") (name "unconnected-(U7-P$14-Pad14)") (class "Default")
      (node (ref "U7") (pin "14") (pinfunction "P$14_14") (pintype "bidirectional"))
    )
    (net (code "174") (name "unconnected-(U7-P$15-Pad15)") (class "Default")
      (node (ref "U7") (pin "15") (pinfunction "P$15_15") (pintype "bidirectional"))
    )
    (net (code "175") (name "unconnected-(U7-P$16-Pad16)") (class "Default")
      (node (ref "U7") (pin "16") (pinfunction "P$16_16") (pintype "bidirectional"))
    )
    (net (code "176") (name "unconnected-(U7-P$17-Pad17)") (class "Default")
      (node (ref "U7") (pin "17") (pinfunction "P$17_17") (pintype "bidirectional"))
    )
    (net (code "177") (name "unconnected-(U7-P$18-Pad18)") (class "Default")
      (node (ref "U7") (pin "18") (pinfunction "P$18_18") (pintype "bidirectional"))
    )
    (net (code "178") (name "unconnected-(U7-P$20-Pad20)") (class "Default")
      (node (ref "U7") (pin "20") (pinfunction "P$20_20") (pintype "bidirectional"))
    )
    (net (code "179") (name "unconnected-(U7-P$21-Pad21)") (class "Default")
      (node (ref "U7") (pin "21") (pinfunction "P$21_21") (pintype "bidirectional"))
    )
    (net (code "180") (name "unconnected-(U7-P$23-Pad23)") (class "Default")
      (node (ref "U7") (pin "23") (pinfunction "P$23_23") (pintype "bidirectional"))
    )
    (net (code "181") (name "unconnected-(U7-P$30-Pad30)") (class "Default")
      (node (ref "U7") (pin "30") (pinfunction "P$30_30") (pintype "bidirectional"))
    )
    (net (code "182") (name "unconnected-(U7-P$38-Pad38)") (class "Default")
      (node (ref "U7") (pin "38") (pinfunction "P$38_38") (pintype "bidirectional"))
    )
    (net (code "183") (name "unconnected-(U7-P$44-Pad44)") (class "Default")
      (node (ref "U7") (pin "44") (pinfunction "P$44_44") (pintype "bidirectional"))
    )
    (net (code "184") (name "unconnected-(U7-P$46-Pad46)") (class "Default")
      (node (ref "U7") (pin "46") (pinfunction "P$46_46") (pintype "bidirectional"))
    )
    (net (code "185") (name "unconnected-(U8-P$13-Pad13)") (class "Default")
      (node (ref "U8") (pin "13") (pinfunction "P$13_13") (pintype "bidirectional"))
    )
    (net (code "186") (name "unconnected-(U8-P$14-Pad14)") (class "Default")
      (node (ref "U8") (pin "14") (pinfunction "P$14_14") (pintype "bidirectional"))
    )
    (net (code "187") (name "unconnected-(U8-P$15-Pad15)") (class "Default")
      (node (ref "U8") (pin "15") (pinfunction "P$15_15") (pintype "bidirectional"))
    )
    (net (code "188") (name "unconnected-(U8-P$16-Pad16)") (class "Default")
      (node (ref "U8") (pin "16") (pinfunction "P$16_16") (pintype "bidirectional"))
    )
    (net (code "189") (name "unconnected-(U8-P$17-Pad17)") (class "Default")
      (node (ref "U8") (pin "17") (pinfunction "P$17_17") (pintype "bidirectional"))
    )
    (net (code "190") (name "unconnected-(U8-P$18-Pad18)") (class "Default")
      (node (ref "U8") (pin "18") (pinfunction "P$18_18") (pintype "bidirectional"))
    )
    (net (code "191") (name "unconnected-(U8-P$20-Pad20)") (class "Default")
      (node (ref "U8") (pin "20") (pinfunction "P$20_20") (pintype "bidirectional"))
    )
    (net (code "192") (name "unconnected-(U8-P$21-Pad21)") (class "Default")
      (node (ref "U8") (pin "21") (pinfunction "P$21_21") (pintype "bidirectional"))
    )
    (net (code "193") (name "unconnected-(U8-P$23-Pad23)") (class "Default")
      (node (ref "U8") (pin "23") (pinfunction "P$23_23") (pintype "bidirectional"))
    )
    (net (code "194") (name "unconnected-(U8-P$30-Pad30)") (class "Default")
      (node (ref "U8") (pin "30") (pinfunction "P$30_30") (pintype "bidirectional"))
    )
    (net (code "195") (name "unconnected-(U8-P$33-Pad33)") (class "Default")
      (node (ref "U8") (pin "33") (pinfunction "P$33_33") (pintype "bidirectional"))
    )
    (net (code "196") (name "unconnected-(U8-P$38-Pad38)") (class "Default")
      (node (ref "U8") (pin "38") (pinfunction "P$38_38") (pintype "bidirectional"))
    )
    (net (code "197") (name "unconnected-(U8-P$44-Pad44)") (class "Default")
      (node (ref "U8") (pin "44") (pinfunction "P$44_44") (pintype "bidirectional"))
    )
    (net (code "198") (name "unconnected-(U8-P$46-Pad46)") (class "Default")
      (node (ref "U8") (pin "46") (pinfunction "P$46_46") (pintype "bidirectional"))
    )
    (net (code "199") (name "unconnected-(U9-Pad3)") (class "Default")
      (node (ref "U9") (pin "3") (pinfunction "3_3") (pintype "bidirectional"))
    )
    (net (code "200") (name "unconnected-(U9-Pad4)") (class "Default")
      (node (ref "U9") (pin "4") (pinfunction "4_4") (pintype "bidirectional"))
    )
    (net (code "201") (name "unconnected-(U9-Pad6)") (class "Default")
      (node (ref "U9") (pin "6") (pinfunction "6_6") (pintype "bidirectional"))
    )
    (net (code "202") (name "unconnected-(U9-Pad10)") (class "Default")
      (node (ref "U9") (pin "10") (pinfunction "10_10") (pintype "input"))
    )
    (net (code "203") (name "unconnected-(U9-Pad11)") (class "Default")
      (node (ref "U9") (pin "11") (pinfunction "11_11") (pintype "bidirectional"))
    )
    (net (code "204") (name "unconnected-(U9-Pad28)") (class "Default")
      (node (ref "U9") (pin "28") (pinfunction "28_28") (pintype "bidirectional"))
    )
    (net (code "205") (name "unconnected-(U9-Pad30)") (class "Default")
      (node (ref "U9") (pin "30") (pinfunction "30_30") (pintype "bidirectional"))
    )
    (net (code "206") (name "unconnected-(U9-Pad41)") (class "Default")
      (node (ref "U9") (pin "41") (pinfunction "41_41") (pintype "bidirectional"))
    )
    (net (code "207") (name "unconnected-(U9-Pad43)") (class "Default")
      (node (ref "U9") (pin "43") (pinfunction "43_43") (pintype "bidirectional"))
    )
    (net (code "208") (name "unconnected-(U9-Pad44)") (class "Default")
      (node (ref "U9") (pin "44") (pinfunction "44_44") (pintype "bidirectional"))
    )
    (net (code "209") (name "unconnected-(U9-Pad45)") (class "Default")
      (node (ref "U9") (pin "45") (pinfunction "45_45") (pintype "bidirectional"))
    )
    (net (code "210") (name "unconnected-(U9-Pad46)") (class "Default")
      (node (ref "U9") (pin "46") (pinfunction "46_46") (pintype "bidirectional"))
    )
    (net (code "211") (name "unconnected-(U9-Pad47)") (class "Default")
      (node (ref "U9") (pin "47") (pinfunction "47_47") (pintype "bidirectional"))
    )
    (net (code "212") (name "unconnected-(U9-Pad48)") (class "Default")
      (node (ref "U9") (pin "48") (pinfunction "48_48") (pintype "bidirectional"))
    )
    (net (code "213") (name "unconnected-(U9-Pad51)") (class "Default")
      (node (ref "U9") (pin "51") (pinfunction "51_51") (pintype "bidirectional"))
    )
    (net (code "214") (name "unconnected-(U9-Pad52)") (class "Default")
      (node (ref "U9") (pin "52") (pinfunction "52_52") (pintype "output"))
    )
    (net (code "215") (name "unconnected-(U9-Pad59)") (class "Default")
      (node (ref "U9") (pin "59") (pinfunction "59_59") (pintype "bidirectional"))
    )
    (net (code "216") (name "unconnected-(U9-Pad60)") (class "Default")
      (node (ref "U9") (pin "60") (pinfunction "60_60") (pintype "bidirectional"))
    )
    (net (code "217") (name "unconnected-(U9-Pad61)") (class "Default")
      (node (ref "U9") (pin "61") (pinfunction "61_61") (pintype "bidirectional"))
    )
    (net (code "218") (name "unconnected-(U10-P$3-Pad3)") (class "Default")
      (node (ref "U10") (pin "3") (pinfunction "P$3_3") (pintype "no_connect"))
    )
    (net (code "219") (name "unconnected-(X7-Pad2)") (class "Default")
      (node (ref "X7") (pin "2") (pinfunction "2_2") (pintype "bidirectional"))
    )
    (net (code "220") (name "unconnected-(X7-Pad6)") (class "Default")
      (node (ref "X7") (pin "6") (pinfunction "6_6") (pintype "bidirectional"))
    )
    (net (code "221") (name "unconnected-(X7-Pad8)") (class "Default")
      (node (ref "X7") (pin "8") (pinfunction "8_8") (pintype "bidirectional"))
    )
    (net (code "222") (name "{slash}RST") (class "Default")
      (node (ref "R40") (pin "2") (pinfunction "2_2") (pintype "passive"))
      (node (ref "R44") (pin "1") (pinfunction "1_1") (pintype "passive"))
      (node (ref "U11") (pin "4") (pinfunction "P$4_4") (pintype "output"))
      (node (ref "U9") (pin "58") (pinfunction "58_58") (pintype "input"))
    )
  )
)
